# New_Gyro_4_0.net
KiCad netlist of a schematic drawn in Altium Designer
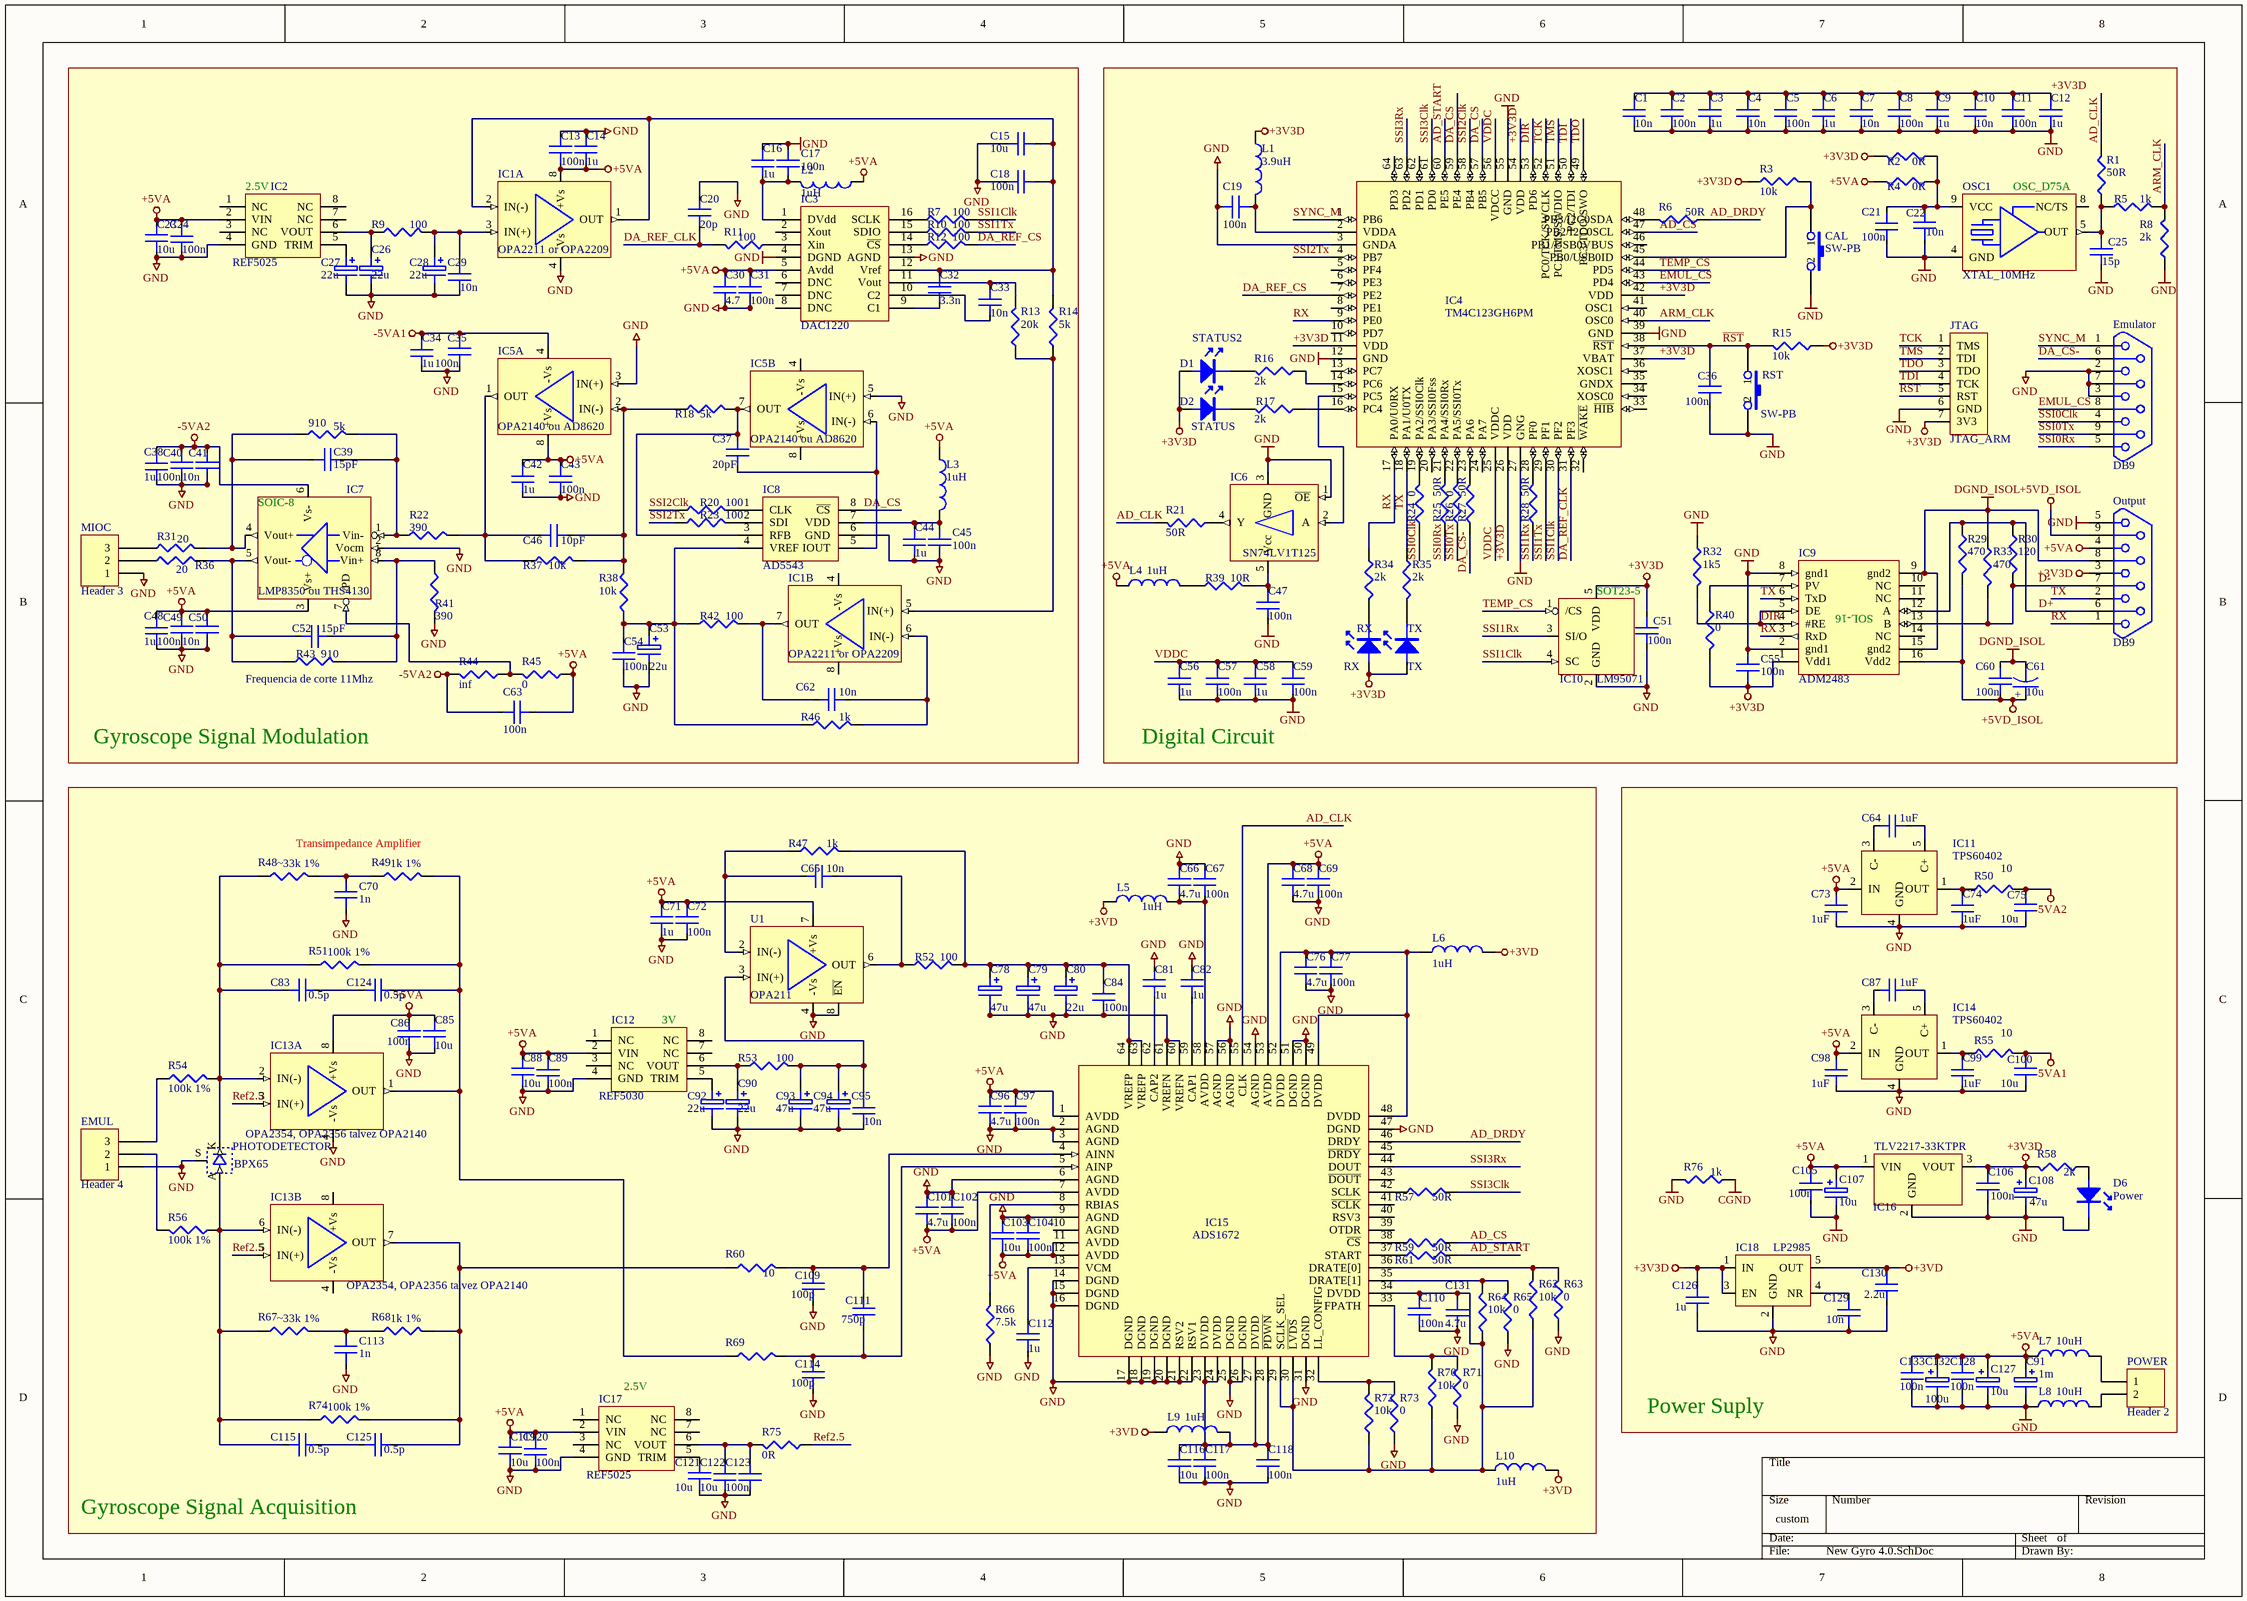
[diagram p0: New Gyro 4.0.SchDoc]

(export (version "E")
  (design (tool "Eeschema 10.0.6"))
  (components
    (comp (ref "910")
      (value "5k")
      (footprint "0805")
      (description "Resistor Thick film 1%")
      (libsource (lib "*") (part "R08"))
    )
    (comp (ref "C1")
      (value "10n")
      (footprint "0805-cap")
      (description "Capacitor Thick film")
      (libsource (lib "*") (part "CAP"))
    )
    (comp (ref "C2")
      (value "100n")
      (footprint "0805-cap")
      (description "Capacitor Thick film")
      (libsource (lib "*") (part "CAP"))
    )
    (comp (ref "C3")
      (value "1u")
      (footprint "0805-cap")
      (description "Capacitor Thick film")
      (libsource (lib "*") (part "CAP"))
    )
    (comp (ref "C4")
      (value "10n")
      (footprint "0805-cap")
      (description "Capacitor Thick film")
      (libsource (lib "*") (part "CAP"))
    )
    (comp (ref "C5")
      (value "100n")
      (footprint "0805-cap")
      (description "Capacitor Thick film")
      (libsource (lib "*") (part "CAP"))
    )
    (comp (ref "C6")
      (value "1u")
      (footprint "0805-cap")
      (description "Capacitor Thick film")
      (libsource (lib "*") (part "CAP"))
    )
    (comp (ref "C7")
      (value "10n")
      (footprint "0805-cap")
      (description "Capacitor Thick film")
      (libsource (lib "*") (part "CAP"))
    )
    (comp (ref "C8")
      (value "100n")
      (footprint "0805-cap")
      (description "Capacitor Thick film")
      (libsource (lib "*") (part "CAP"))
    )
    (comp (ref "C9")
      (value "1u")
      (footprint "0805-cap")
      (description "Capacitor Thick film")
      (libsource (lib "*") (part "CAP"))
    )
    (comp (ref "C10")
      (value "10n")
      (footprint "0805-cap")
      (description "Capacitor Thick film")
      (libsource (lib "*") (part "CAP"))
    )
    (comp (ref "C11")
      (value "100n")
      (footprint "0805-cap")
      (description "Capacitor Thick film")
      (libsource (lib "*") (part "CAP"))
    )
    (comp (ref "C12")
      (value "1u")
      (footprint "0805-cap")
      (description "Capacitor Thick film")
      (libsource (lib "*") (part "CAP"))
    )
    (comp (ref "C13")
      (value "100n")
      (footprint "0805-cap")
      (description "Capacitor Thick film")
      (libsource (lib "*") (part "CAP"))
    )
    (comp (ref "C14")
      (value "1u")
      (footprint "0805-cap")
      (description "Capacitor Thick film")
      (libsource (lib "*") (part "CAP"))
    )
    (comp (ref "C15")
      (value "10u")
      (footprint "0805-cap")
      (description "Capacitor Thick film")
      (libsource (lib "*") (part "CAP"))
    )
    (comp (ref "C16")
      (value "1u")
      (footprint "0805-cap")
      (description "Capacitor Thick film")
      (libsource (lib "*") (part "CAP"))
    )
    (comp (ref "C17")
      (value "100n")
      (footprint "0805-cap")
      (description "Capacitor Thick film")
      (libsource (lib "*") (part "CAP"))
    )
    (comp (ref "C18")
      (value "100n")
      (footprint "0805-cap")
      (description "Capacitor Thick film")
      (libsource (lib "*") (part "CAP"))
    )
    (comp (ref "C19")
      (value "100n")
      (footprint "0805-cap")
      (description "Capacitor Thick film")
      (libsource (lib "*") (part "CAP"))
    )
    (comp (ref "C20")
      (value "20p")
      (footprint "0805-cap")
      (description "Capacitor Thick film")
      (libsource (lib "*") (part "CAP"))
    )
    (comp (ref "C21")
      (value "100n")
      (footprint "0805-cap")
      (description "Capacitor Thick film")
      (libsource (lib "*") (part "CAP"))
    )
    (comp (ref "C22")
      (value "10n")
      (footprint "0805-cap")
      (description "Capacitor Thick film")
      (libsource (lib "*") (part "CAP"))
    )
    (comp (ref "C23")
      (value "10u")
      (footprint "0805-cap")
      (description "Capacitor Thick film")
      (libsource (lib "*") (part "CAP"))
    )
    (comp (ref "C24")
      (value "100n")
      (footprint "0805-cap")
      (description "Capacitor Thick film")
      (libsource (lib "*") (part "CAP"))
    )
    (comp (ref "C25")
      (value "15p")
      (footprint "0805-cap")
      (description "Capacitor Thick film")
      (libsource (lib "*") (part "CAP"))
    )
    (comp (ref "C26")
      (value "22u")
      (footprint "0805-cap")
      (description "Capacitor Tântalo SMD")
      (libsource (lib "*") (part "CAPT"))
    )
    (comp (ref "C27")
      (value "22u")
      (footprint "0805-cap")
      (description "Capacitor Tântalo SMD")
      (libsource (lib "*") (part "CAPT"))
    )
    (comp (ref "C28")
      (value "22u")
      (footprint "0805-cap")
      (description "Capacitor Tântalo SMD")
      (libsource (lib "*") (part "CAPT"))
    )
    (comp (ref "C29")
      (value "10n")
      (footprint "0805-cap")
      (description "Capacitor Thick film")
      (libsource (lib "*") (part "CAP"))
    )
    (comp (ref "C30")
      (value "4.7")
      (footprint "0805-cap")
      (description "Capacitor Thick film")
      (libsource (lib "*") (part "CAP"))
    )
    (comp (ref "C31")
      (value "100n")
      (footprint "0805-cap")
      (description "Capacitor Thick film")
      (libsource (lib "*") (part "CAP"))
    )
    (comp (ref "C32")
      (value "3.3n")
      (footprint "0805-cap")
      (description "Capacitor Thick film")
      (libsource (lib "*") (part "CAP"))
    )
    (comp (ref "C33")
      (value "10n")
      (footprint "0805-cap")
      (description "Capacitor Thick film")
      (libsource (lib "*") (part "CAP"))
    )
    (comp (ref "C34")
      (value "1u")
      (footprint "0805-cap")
      (description "Capacitor Thick film")
      (libsource (lib "*") (part "CAP"))
    )
    (comp (ref "C35")
      (value "100n")
      (footprint "0805-cap")
      (description "Capacitor Thick film")
      (libsource (lib "*") (part "CAP"))
    )
    (comp (ref "C36")
      (value "100n")
      (footprint "0805-cap")
      (description "Capacitor Thick film")
      (libsource (lib "*") (part "CAP"))
    )
    (comp (ref "C37")
      (value "20pF")
      (footprint "0805-cap")
      (description "Capacitor Thick film")
      (libsource (lib "*") (part "CAP"))
    )
    (comp (ref "C38")
      (value "1u")
      (footprint "0805-cap")
      (description "Capacitor Thick film")
      (libsource (lib "*") (part "CAP"))
    )
    (comp (ref "C39")
      (value "15pF")
      (footprint "0805-cap")
      (description "Capacitor Thick film")
      (libsource (lib "*") (part "CAP"))
    )
    (comp (ref "C40")
      (value "100n")
      (footprint "0805-cap")
      (description "Capacitor Thick film")
      (libsource (lib "*") (part "CAP"))
    )
    (comp (ref "C41")
      (value "10n")
      (footprint "0805-cap")
      (description "Capacitor Thick film")
      (libsource (lib "*") (part "CAP"))
    )
    (comp (ref "C42")
      (value "1u")
      (footprint "0805-cap")
      (description "Capacitor Thick film")
      (libsource (lib "*") (part "CAP"))
    )
    (comp (ref "C43")
      (value "100n")
      (footprint "0805-cap")
      (description "Capacitor Thick film")
      (libsource (lib "*") (part "CAP"))
    )
    (comp (ref "C44")
      (value "1u")
      (footprint "0805-cap")
      (description "Capacitor Thick film")
      (libsource (lib "*") (part "CAP"))
    )
    (comp (ref "C45")
      (value "100n")
      (footprint "0805-cap")
      (description "Capacitor Thick film")
      (libsource (lib "*") (part "CAP"))
    )
    (comp (ref "C46")
      (value "10pF")
      (footprint "0805-cap")
      (description "Capacitor Thick film")
      (libsource (lib "*") (part "CAP"))
    )
    (comp (ref "C47")
      (value "100n")
      (footprint "0805-cap")
      (description "Capacitor Thick film")
      (libsource (lib "*") (part "CAP"))
    )
    (comp (ref "C48")
      (value "1u")
      (footprint "0805-cap")
      (description "Capacitor Thick film")
      (libsource (lib "*") (part "CAP"))
    )
    (comp (ref "C49")
      (value "100n")
      (footprint "0805-cap")
      (description "Capacitor Thick film")
      (libsource (lib "*") (part "CAP"))
    )
    (comp (ref "C50")
      (value "10n")
      (footprint "0805-cap")
      (description "Capacitor Thick film")
      (libsource (lib "*") (part "CAP"))
    )
    (comp (ref "C51")
      (value "100n")
      (footprint "0805-cap")
      (description "Capacitor Thick film")
      (libsource (lib "*") (part "CAP"))
    )
    (comp (ref "C52")
      (value "15pF")
      (footprint "0805-cap")
      (description "Capacitor Thick film")
      (libsource (lib "*") (part "CAP"))
    )
    (comp (ref "C53")
      (value "22u")
      (footprint "0805-cap")
      (description "Capacitor Tântalo SMD")
      (libsource (lib "*") (part "CAPT"))
    )
    (comp (ref "C54")
      (value "100n")
      (footprint "0805-cap")
      (description "Capacitor Thick film")
      (libsource (lib "*") (part "CAP"))
    )
    (comp (ref "C55")
      (value "100n")
      (footprint "0805-cap")
      (description "Capacitor Thick film")
      (libsource (lib "*") (part "CAP"))
    )
    (comp (ref "C56")
      (value "1u")
      (footprint "0805-cap")
      (description "Capacitor Thick film")
      (libsource (lib "*") (part "CAP"))
    )
    (comp (ref "C57")
      (value "100n")
      (footprint "0805-cap")
      (description "Capacitor Thick film")
      (libsource (lib "*") (part "CAP"))
    )
    (comp (ref "C58")
      (value "1u")
      (footprint "0805-cap")
      (description "Capacitor Thick film")
      (libsource (lib "*") (part "CAP"))
    )
    (comp (ref "C59")
      (value "100n")
      (footprint "0805-cap")
      (description "Capacitor Thick film")
      (libsource (lib "*") (part "CAP"))
    )
    (comp (ref "C60")
      (value "100n")
      (footprint "0805-cap")
      (description "Capacitor Thick film")
      (libsource (lib "*") (part "CAP"))
    )
    (comp (ref "C61")
      (value "10u")
      (footprint "0805-cap")
      (description "Capacitor Tântalo")
      (libsource (lib "*") (part "CAPACITOR POL"))
    )
    (comp (ref "C62")
      (value "10n")
      (footprint "0805-cap")
      (description "Capacitor Thick film")
      (libsource (lib "*") (part "CAP"))
    )
    (comp (ref "C63")
      (value "100n")
      (footprint "0805-cap")
      (description "Capacitor Thick film")
      (libsource (lib "*") (part "CAP"))
    )
    (comp (ref "C64")
      (value "1uF")
      (footprint "0805-cap")
      (description "Capacitor Thick film")
      (libsource (lib "*") (part "CAP"))
    )
    (comp (ref "C65")
      (value "10n")
      (footprint "0805-cap")
      (description "Capacitor Thick film")
      (libsource (lib "*") (part "CAP"))
    )
    (comp (ref "C66")
      (value "4.7u")
      (footprint "0805-cap")
      (description "Capacitor Thick film")
      (libsource (lib "*") (part "CAP"))
    )
    (comp (ref "C67")
      (value "100n")
      (footprint "0805-cap")
      (description "Capacitor Thick film")
      (libsource (lib "*") (part "CAP"))
    )
    (comp (ref "C68")
      (value "4.7u")
      (footprint "0805-cap")
      (description "Capacitor Thick film")
      (libsource (lib "*") (part "CAP"))
    )
    (comp (ref "C69")
      (value "100n")
      (footprint "0805-cap")
      (description "Capacitor Thick film")
      (libsource (lib "*") (part "CAP"))
    )
    (comp (ref "C70")
      (value "1n")
      (footprint "0805-cap")
      (description "Capacitor Thick film")
      (libsource (lib "*") (part "CAP"))
    )
    (comp (ref "C71")
      (value "1u")
      (footprint "0805-cap")
      (description "Capacitor Thick film")
      (libsource (lib "*") (part "CAP"))
    )
    (comp (ref "C72")
      (value "100n")
      (footprint "0805-cap")
      (description "Capacitor Thick film")
      (libsource (lib "*") (part "CAP"))
    )
    (comp (ref "C73")
      (value "1uF")
      (footprint "0805-cap")
      (description "Capacitor Thick film")
      (libsource (lib "*") (part "CAP"))
    )
    (comp (ref "C74")
      (value "1uF")
      (footprint "0805-cap")
      (description "Capacitor Thick film")
      (libsource (lib "*") (part "CAP"))
    )
    (comp (ref "C75")
      (value "10u")
      (footprint "0805-cap")
      (description "Capacitor Thick film")
      (libsource (lib "*") (part "CAP"))
    )
    (comp (ref "C76")
      (value "4.7u")
      (footprint "0805-cap")
      (description "Capacitor Thick film")
      (libsource (lib "*") (part "CAP"))
    )
    (comp (ref "C77")
      (value "100n")
      (footprint "0805-cap")
      (description "Capacitor Thick film")
      (libsource (lib "*") (part "CAP"))
    )
    (comp (ref "C78")
      (value "47u")
      (footprint "0805-cap")
      (description "Capacitor Tântalo SMD")
      (libsource (lib "*") (part "CAPT"))
    )
    (comp (ref "C79")
      (value "47u")
      (footprint "0805-cap")
      (description "Capacitor Tântalo SMD")
      (libsource (lib "*") (part "CAPT"))
    )
    (comp (ref "C80")
      (value "22u")
      (footprint "0805-cap")
      (description "Capacitor Tântalo SMD")
      (libsource (lib "*") (part "CAPT"))
    )
    (comp (ref "C81")
      (value "1u")
      (footprint "0805-cap")
      (description "Capacitor Thick film")
      (libsource (lib "*") (part "CAP"))
    )
    (comp (ref "C82")
      (value "1u")
      (footprint "0805-cap")
      (description "Capacitor Thick film")
      (libsource (lib "*") (part "CAP"))
    )
    (comp (ref "C83")
      (value "0.5p")
      (footprint "0805-cap")
      (description "Capacitor Thick film")
      (libsource (lib "*") (part "CAP"))
    )
    (comp (ref "C84")
      (value "100n")
      (footprint "0805-cap")
      (description "Capacitor Thick film")
      (libsource (lib "*") (part "CAP"))
    )
    (comp (ref "C85")
      (value "10u")
      (footprint "0805-cap")
      (description "Capacitor Thick film")
      (libsource (lib "*") (part "CAP"))
    )
    (comp (ref "C86")
      (value "100n")
      (footprint "0805-cap")
      (description "Capacitor Thick film")
      (libsource (lib "*") (part "CAP"))
    )
    (comp (ref "C87")
      (value "1uF")
      (footprint "0805-cap")
      (description "Capacitor Thick film")
      (libsource (lib "*") (part "CAP"))
    )
    (comp (ref "C88")
      (value "10u")
      (footprint "0805-cap")
      (description "Capacitor Thick film")
      (libsource (lib "*") (part "CAP"))
    )
    (comp (ref "C89")
      (value "100n")
      (footprint "0805-cap")
      (description "Capacitor Thick film")
      (libsource (lib "*") (part "CAP"))
    )
    (comp (ref "C90")
      (value "22u")
      (footprint "0805-cap")
      (description "Capacitor Tântalo SMD")
      (libsource (lib "*") (part "CAPT"))
    )
    (comp (ref "C91")
      (value "1m")
      (footprint "CAP 1000u - duplicate")
      (description "Capacitor Tântalo SMD")
      (libsource (lib "*") (part "CAPT"))
    )
    (comp (ref "C92")
      (value "22u")
      (footprint "0805-cap")
      (description "Capacitor Tântalo SMD")
      (libsource (lib "*") (part "CAPT"))
    )
    (comp (ref "C93")
      (value "47u")
      (footprint "0805-cap")
      (description "Capacitor Tântalo SMD")
      (libsource (lib "*") (part "CAPT"))
    )
    (comp (ref "C94")
      (value "47u")
      (footprint "0805-cap")
      (description "Capacitor Tântalo SMD")
      (libsource (lib "*") (part "CAPT"))
    )
    (comp (ref "C95")
      (value "10n")
      (footprint "0805-cap")
      (description "Capacitor Thick film")
      (libsource (lib "*") (part "CAP"))
    )
    (comp (ref "C96")
      (value "4.7u")
      (footprint "0805-cap")
      (description "Capacitor Thick film")
      (libsource (lib "*") (part "CAP"))
    )
    (comp (ref "C97")
      (value "100n")
      (footprint "0805-cap")
      (description "Capacitor Thick film")
      (libsource (lib "*") (part "CAP"))
    )
    (comp (ref "C98")
      (value "1uF")
      (footprint "0805-cap")
      (description "Capacitor Thick film")
      (libsource (lib "*") (part "CAP"))
    )
    (comp (ref "C99")
      (value "1uF")
      (footprint "0805-cap")
      (description "Capacitor Thick film")
      (libsource (lib "*") (part "CAP"))
    )
    (comp (ref "C100")
      (value "10u")
      (footprint "0805-cap")
      (description "Capacitor Thick film")
      (libsource (lib "*") (part "CAP"))
    )
    (comp (ref "C101")
      (value "4.7u")
      (footprint "0805-cap")
      (description "Capacitor Thick film")
      (libsource (lib "*") (part "CAP"))
    )
    (comp (ref "C102")
      (value "100n")
      (footprint "0805-cap")
      (description "Capacitor Thick film")
      (libsource (lib "*") (part "CAP"))
    )
    (comp (ref "C103")
      (value "10u")
      (footprint "0805-cap")
      (description "Capacitor Thick film")
      (libsource (lib "*") (part "CAP"))
    )
    (comp (ref "C104")
      (value "100n")
      (footprint "0805-cap")
      (description "Capacitor Thick film")
      (libsource (lib "*") (part "CAP"))
    )
    (comp (ref "C105")
      (value "100n")
      (footprint "0805-cap")
      (description "Capacitor Thick film")
      (libsource (lib "*") (part "CAP"))
    )
    (comp (ref "C106")
      (value "100n")
      (footprint "0805-cap")
      (description "Capacitor Thick film")
      (libsource (lib "*") (part "CAP"))
    )
    (comp (ref "C107")
      (value "10u")
      (footprint "0805-cap")
      (description "Capacitor Tântalo SMD")
      (libsource (lib "*") (part "CAPT"))
    )
    (comp (ref "C108")
      (value "47u")
      (footprint "0805-cap")
      (description "Capacitor Tântalo SMD")
      (libsource (lib "*") (part "CAPT"))
    )
    (comp (ref "C109")
      (value "100p")
      (footprint "0805-cap")
      (description "Capacitor Thick film")
      (libsource (lib "*") (part "CAP"))
    )
    (comp (ref "C110")
      (value "100n")
      (footprint "0805-cap")
      (description "Capacitor Thick film")
      (libsource (lib "*") (part "CAP"))
    )
    (comp (ref "C111")
      (value "750p")
      (footprint "0805-cap")
      (description "Capacitor Thick film")
      (libsource (lib "*") (part "CAP"))
    )
    (comp (ref "C112")
      (value "1u")
      (footprint "0805-cap")
      (description "Capacitor Thick film")
      (libsource (lib "*") (part "CAP"))
    )
    (comp (ref "C113")
      (value "1n")
      (footprint "0805-cap")
      (description "Capacitor Thick film")
      (libsource (lib "*") (part "CAP"))
    )
    (comp (ref "C114")
      (value "100p")
      (footprint "0805-cap")
      (description "Capacitor Thick film")
      (libsource (lib "*") (part "CAP"))
    )
    (comp (ref "C115")
      (value "0.5p")
      (footprint "0805-cap")
      (description "Capacitor Thick film")
      (libsource (lib "*") (part "CAP"))
    )
    (comp (ref "C116")
      (value "10u")
      (footprint "0805-cap")
      (description "Capacitor Thick film")
      (libsource (lib "*") (part "CAP"))
    )
    (comp (ref "C117")
      (value "100n")
      (footprint "0805-cap")
      (description "Capacitor Thick film")
      (libsource (lib "*") (part "CAP"))
    )
    (comp (ref "C118")
      (value "100n")
      (footprint "0805-cap")
      (description "Capacitor Thick film")
      (libsource (lib "*") (part "CAP"))
    )
    (comp (ref "C119")
      (value "10u")
      (footprint "0805-cap")
      (description "Capacitor Thick film")
      (libsource (lib "*") (part "CAP"))
    )
    (comp (ref "C120")
      (value "100n")
      (footprint "0805-cap")
      (description "Capacitor Thick film")
      (libsource (lib "*") (part "CAP"))
    )
    (comp (ref "C121")
      (value "10u")
      (footprint "0805-cap")
      (description "Capacitor Thick film")
      (libsource (lib "*") (part "CAP"))
    )
    (comp (ref "C122")
      (value "10u")
      (footprint "0805-cap")
      (description "Capacitor Thick film")
      (libsource (lib "*") (part "CAP"))
    )
    (comp (ref "C123")
      (value "100n")
      (footprint "0805-cap")
      (description "Capacitor Thick film")
      (libsource (lib "*") (part "CAP"))
    )
    (comp (ref "C124")
      (value "0.5p")
      (footprint "0805-cap")
      (description "Capacitor Thick film")
      (libsource (lib "*") (part "CAP"))
    )
    (comp (ref "C125")
      (value "0.5p")
      (footprint "0805-cap")
      (description "Capacitor Thick film")
      (libsource (lib "*") (part "CAP"))
    )
    (comp (ref "C126")
      (value "1u")
      (footprint "0805-cap")
      (description "Capacitor Thick film")
      (libsource (lib "*") (part "CAP"))
    )
    (comp (ref "C127")
      (value "10u")
      (footprint "0805-cap")
      (description "Capacitor Tântalo SMD")
      (libsource (lib "*") (part "CAPT"))
    )
    (comp (ref "C128")
      (value "100n")
      (footprint "0805-cap")
      (description "Capacitor Thick film")
      (libsource (lib "*") (part "CAP"))
    )
    (comp (ref "C129")
      (value "10n")
      (footprint "0805-cap")
      (description "Capacitor Thick film")
      (libsource (lib "*") (part "CAP"))
    )
    (comp (ref "C130")
      (value "2.2u")
      (footprint "0805-cap")
      (description "Capacitor Thick film")
      (libsource (lib "*") (part "CAP"))
    )
    (comp (ref "C131")
      (value "4.7u")
      (footprint "0805-cap")
      (description "Capacitor Thick film")
      (libsource (lib "*") (part "CAP"))
    )
    (comp (ref "C132")
      (value "100u")
      (footprint "1206_Capacitor")
      (description "Capacitor Tântalo SMD")
      (libsource (lib "*") (part "CAPT"))
    )
    (comp (ref "C133")
      (value "100n")
      (footprint "0805-cap")
      (description "Capacitor Thick film")
      (libsource (lib "*") (part "CAP"))
    )
    (comp (ref "CAL") (value "SW-PB") (footprint "SW SMD") (libsource (lib "Gyro") (part "SW")))
    (comp (ref "D1")
      (value "STATUS2")
      (footprint "LED")
      (description "SMD LED 0805 package")
      (libsource (lib "*") (part "LED_CV"))
    )
    (comp (ref "D2")
      (value "STATUS")
      (footprint "LED")
      (description "SMD LED 0805 package")
      (libsource (lib "*") (part "LED_CV"))
    )
    (comp (ref "D6")
      (value "Power")
      (footprint "LED")
      (description "SMD LED 0805 package")
      (libsource (lib "*") (part "LED_CV"))
    )
    (comp (ref "EMUL")
      (value "Header 4")
      (footprint "HDR1X3")
      (description "Header, 3-Pin")
      (fields (field (name "PUBLISHER") "Altium Limited"))
      (libsource (lib "Miscellaneous Connectors") (part "Header 3"))
    )
    (comp (ref "Emulator") (value "DB9") (footprint "DB9FLW") (libsource (lib "*") (part "DB9")))
    (comp (ref "IC1")
      (value "OPA2211 or OPA2209")
      (footprint "MSOP8")
      (libsource (lib "") (part "AMPOPDUAL_1"))
    )
    (comp (ref "IC2") (value "REF5025") (footprint "MSOP8") (libsource (lib "Gyro") (part "ADR440AMZ")))
    (comp (ref "IC3") (value "DAC1220") (footprint "DBQ 16 TI") (libsource (lib "Gyro") (part "DAC1220")))
    (comp (ref "IC4")
      (value "TM4C123GH6PM")
      (footprint "PQFP64")
      (description "ARM M4F Texas")
      (libsource (lib "Gyro") (part "TM4C123GH6PM"))
    )
    (comp (ref "IC5")
      (value "OPA2140 ou AD8620")
      (footprint "MSOP8")
      (libsource (lib "Gyro") (part "AMPOPDUAL"))
    )
    (comp (ref "IC6")
      (value "SN74LV1T125")
      (footprint "SOT-23-5")
      (description "Single Power Supply Single Buffer Gate with 3-State Output CMOS Logic  Level Shifter")
      (libsource (lib "Gyro") (part "SN74LV1T125"))
    )
    (comp (ref "IC7")
      (value "LMP8350 ou THS4130")
      (footprint "SO-8")
      (description "WIDEBAND, LOW-DISTORTION, FULLY DIFFERENTIAL AMPLIFIER")
      (libsource (lib "*") (part "THS4505"))
    )
    (comp (ref "IC8")
      (value "AD5543")
      (footprint "MSOP8")
      (description "16 Bit SPI DAC")
      (libsource (lib "Gyro") (part "AD5543"))
    )
    (comp (ref "IC9") (value "ADM2483") (footprint "SOL-16") (libsource (lib "*") (part "ADM2483")))
    (comp (ref "IC10") (value "LM95071") (footprint "SOT-23") (libsource (lib "*") (part "LM95071")))
    (comp (ref "IC11")
      (value "TPS60402")
      (footprint "PlacaGiro_atualizada:SOT-23-5")
      (description "Charge Pump Inverter")
      (libsource (lib "Gyro") (part "TPS60401"))
    )
    (comp (ref "IC12") (value "REF5030") (footprint "MSOP8") (libsource (lib "Gyro") (part "ADR440AMZ")))
    (comp (ref "IC13")
      (value "OPA2354, OPA2356 talvez OPA2140")
      (footprint "MSOP8")
      (libsource (lib "") (part "AMPOPDUAL_1"))
    )
    (comp (ref "IC14")
      (value "TPS60402")
      (footprint "PlacaGiro_atualizada:SOT-23-5")
      (description "Charge Pump Inverter")
      (libsource (lib "Gyro") (part "TPS60401"))
    )
    (comp (ref "IC15")
      (value "ADS1672")
      (footprint "TM4C123GH6PM_PQFP64")
      (description "625kSPS, 24-Bit Analog-to-Digital Converter")
      (libsource (lib "Gyro") (part "ADS1672"))
    )
    (comp (ref "IC16")
      (value "TLV2217-33KTPR")
      (footprint "KTP")
      (libsource (lib "*") (part "LM78L05AC/TO3_0"))
    )
    (comp (ref "IC17") (value "REF5025") (footprint "MSOP8") (libsource (lib "Gyro") (part "ADR440AMZ")))
    (comp (ref "IC18")
      (value "LP2985")
      (footprint "PlacaGiro_atualizada:SOT-23-5")
      (libsource (lib "Gyro") (part "LP2985"))
    )
    (comp (ref "JTAG") (value "JTAG_ARM") (footprint "HDR1X7") (libsource (lib "Gyro") (part "JTAG_ARM")))
    (comp (ref "L1") (value "3.9uH") (footprint "0805") (libsource (lib "*") (part "L")))
    (comp (ref "L2") (value "1uH") (footprint "0805") (libsource (lib "*") (part "L")))
    (comp (ref "L3") (value "1uH") (footprint "0805") (libsource (lib "*") (part "L")))
    (comp (ref "L4") (value "1uH") (footprint "0805") (libsource (lib "*") (part "L")))
    (comp (ref "L5") (value "1uH") (footprint "0805") (libsource (lib "*") (part "L")))
    (comp (ref "L6") (value "1uH") (footprint "0805") (libsource (lib "*") (part "L")))
    (comp (ref "L7") (value "10uH") (footprint "SPD62") (libsource (lib "*") (part "L")))
    (comp (ref "L8") (value "10uH") (footprint "SPD62") (libsource (lib "*") (part "L")))
    (comp (ref "L9") (value "1uH") (footprint "0805") (libsource (lib "*") (part "L")))
    (comp (ref "L10") (value "1uH") (footprint "0805") (libsource (lib "*") (part "L")))
    (comp (ref "MIOC")
      (value "Header 3")
      (footprint "HDR1X3")
      (description "Header, 3-Pin")
      (fields (field (name "PUBLISHER") "Altium Limited"))
      (libsource (lib "Miscellaneous Connectors") (part "Header 3"))
    )
    (comp (ref "OSC1")
      (value "XTAL_10MHz")
      (footprint "OSC_D75A_")
      (libsource (lib "Gyro") (part "XTAL_D75A"))
    )
    (comp (ref "Output") (value "DB9") (footprint "DB9FLW") (libsource (lib "") (part "DB9_1")))
    (comp (ref "PHOTODETECTOR") (value "BPX65") (footprint "otico") (libsource (lib "*") (part "BYW29-150")))
    (comp (ref "POWER")
      (value "Header 2")
      (footprint "HDR1X2")
      (description "Header, 2-Pin")
      (fields (field (name "PUBLISHER") "Altium Limited"))
      (libsource (lib "Miscellaneous Connectors") (part "Header 2"))
    )
    (comp (ref "R1")
      (value "50R")
      (footprint "0805")
      (description "Resistor")
      (libsource (lib "*") (part "RES"))
    )
    (comp (ref "R2")
      (value "0R")
      (footprint "0805")
      (description "Resistor Thick film 5%")
      (libsource (lib "*") (part "R06"))
    )
    (comp (ref "R3")
      (value "10k")
      (footprint "0805")
      (description "Resistor Thick film 5%")
      (libsource (lib "*") (part "R06"))
    )
    (comp (ref "R4")
      (value "0R")
      (footprint "0805")
      (description "Resistor Thick film 5%")
      (libsource (lib "*") (part "R06"))
    )
    (comp (ref "R5")
      (value "1k")
      (footprint "0805")
      (description "Resistor")
      (libsource (lib "*") (part "RES"))
    )
    (comp (ref "R6")
      (value "50R")
      (footprint "0805")
      (description "Resistor Thick film 1%")
      (libsource (lib "*") (part "R08"))
    )
    (comp (ref "R7")
      (value "100")
      (footprint "0805")
      (description "Resistor Thick film 1%")
      (libsource (lib "*") (part "R08"))
    )
    (comp (ref "R8")
      (value "2k")
      (footprint "0805")
      (description "Resistor")
      (libsource (lib "*") (part "RES"))
    )
    (comp (ref "R9")
      (value "100")
      (footprint "0805")
      (description "Resistor Thick film 1%")
      (libsource (lib "*") (part "R08"))
    )
    (comp (ref "R10")
      (value "100")
      (footprint "0805")
      (description "Resistor Thick film 1%")
      (libsource (lib "*") (part "R08"))
    )
    (comp (ref "R11")
      (value "100")
      (footprint "0805")
      (description "Resistor Thick film 1%")
      (libsource (lib "*") (part "R08"))
    )
    (comp (ref "R12")
      (value "100")
      (footprint "0805")
      (description "Resistor Thick film 1%")
      (libsource (lib "*") (part "R08"))
    )
    (comp (ref "R13")
      (value "20k")
      (footprint "0805")
      (description "Resistor Thick film 1%")
      (libsource (lib "*") (part "R08"))
    )
    (comp (ref "R14")
      (value "5k")
      (footprint "0805")
      (description "Resistor Thick film 1%")
      (libsource (lib "*") (part "R08"))
    )
    (comp (ref "R15")
      (value "10k")
      (footprint "0805")
      (description "Resistor Thick film 5%")
      (libsource (lib "*") (part "R06"))
    )
    (comp (ref "R16")
      (value "2k")
      (footprint "0805")
      (description "Resistor Thick film 5%")
      (libsource (lib "*") (part "R06"))
    )
    (comp (ref "R17")
      (value "2k")
      (footprint "0805")
      (description "Resistor Thick film 5%")
      (libsource (lib "*") (part "R06"))
    )
    (comp (ref "R18")
      (value "5k")
      (footprint "0805")
      (description "Resistor Thick film 1%")
      (libsource (lib "*") (part "R08"))
    )
    (comp (ref "R20")
      (value "100")
      (footprint "0805")
      (description "Resistor Thick film 1%")
      (libsource (lib "*") (part "R08"))
    )
    (comp (ref "R21")
      (value "50R")
      (footprint "0805")
      (description "Resistor")
      (libsource (lib "*") (part "RES"))
    )
    (comp (ref "R22")
      (value "390")
      (footprint "0805")
      (description "Resistor Thick film 1%")
      (libsource (lib "*") (part "R08"))
    )
    (comp (ref "R23")
      (value "100")
      (footprint "0805")
      (description "Resistor Thick film 1%")
      (libsource (lib "*") (part "R08"))
    )
    (comp (ref "R24")
      (value "0")
      (footprint "0805")
      (description "Resistor Thick film 1%")
      (libsource (lib "*") (part "R08"))
    )
    (comp (ref "R25")
      (value "50R")
      (footprint "0805")
      (description "Resistor Thick film 1%")
      (libsource (lib "*") (part "R08"))
    )
    (comp (ref "R26")
      (value "0")
      (footprint "0805")
      (description "Resistor Thick film 1%")
      (libsource (lib "*") (part "R08"))
    )
    (comp (ref "R27")
      (value "50R")
      (footprint "0805")
      (description "Resistor Thick film 1%")
      (libsource (lib "*") (part "R08"))
    )
    (comp (ref "R28")
      (value "50R")
      (footprint "0805")
      (description "Resistor Thick film 1%")
      (libsource (lib "*") (part "R08"))
    )
    (comp (ref "R29")
      (value "470")
      (footprint "0805")
      (description "Resistor Thick film 5%")
      (libsource (lib "*") (part "R06"))
    )
    (comp (ref "R30")
      (value "120")
      (footprint "0805")
      (description "Resistor Thick film 5%")
      (libsource (lib "*") (part "R06"))
    )
    (comp (ref "R31")
      (value "20")
      (footprint "0805")
      (description "Resistor Thick film 5%")
      (libsource (lib "*") (part "R06"))
    )
    (comp (ref "R32")
      (value "1k5")
      (footprint "0805")
      (description "Resistor Thick film 1%")
      (libsource (lib "*") (part "R08"))
    )
    (comp (ref "R33")
      (value "470")
      (footprint "0805")
      (description "Resistor Thick film 5%")
      (libsource (lib "*") (part "R06"))
    )
    (comp (ref "R34")
      (value "2k")
      (footprint "0805")
      (description "Resistor Thick film 5%")
      (libsource (lib "*") (part "R06"))
    )
    (comp (ref "R35")
      (value "2k")
      (footprint "0805")
      (description "Resistor Thick film 5%")
      (libsource (lib "*") (part "R06"))
    )
    (comp (ref "R36")
      (value "20")
      (footprint "0805")
      (description "Resistor Thick film 5%")
      (libsource (lib "*") (part "R06"))
    )
    (comp (ref "R37")
      (value "10k")
      (footprint "0805")
      (description "Resistor Thick film 1%")
      (libsource (lib "*") (part "R08"))
    )
    (comp (ref "R38")
      (value "10k")
      (footprint "0805")
      (description "Resistor Thick film 1%")
      (libsource (lib "*") (part "R08"))
    )
    (comp (ref "R39")
      (value "10R")
      (footprint "0805")
      (description "Resistor")
      (libsource (lib "*") (part "RES"))
    )
    (comp (ref "R40")
      (value "0")
      (footprint "0805")
      (description "Resistor Thick film 1%")
      (libsource (lib "*") (part "R08"))
    )
    (comp (ref "R41")
      (value "390")
      (footprint "0805")
      (description "Resistor Thick film 1%")
      (libsource (lib "*") (part "R08"))
    )
    (comp (ref "R42")
      (value "100")
      (footprint "0805")
      (description "Resistor Thick film 1%")
      (libsource (lib "*") (part "R08"))
    )
    (comp (ref "R43")
      (value "910")
      (footprint "0805")
      (description "Resistor Thick film 1%")
      (libsource (lib "*") (part "R08"))
    )
    (comp (ref "R44")
      (value "inf")
      (footprint "0805")
      (description "Resistor Thick film 1%")
      (libsource (lib "*") (part "R08"))
    )
    (comp (ref "R45")
      (value "0")
      (footprint "0805")
      (description "Resistor Thick film 1%")
      (libsource (lib "*") (part "R08"))
    )
    (comp (ref "R46")
      (value "1k")
      (footprint "0805")
      (description "Resistor Thick film 1%")
      (libsource (lib "*") (part "R08"))
    )
    (comp (ref "R47")
      (value "1k")
      (footprint "0805")
      (description "Resistor Thick film 1%")
      (libsource (lib "*") (part "R08"))
    )
    (comp (ref "R48")
      (value "~33k 1%")
      (footprint "0805")
      (description "Resistor Thick film 1%")
      (libsource (lib "*") (part "R08"))
    )
    (comp (ref "R49")
      (value "1k 1%")
      (footprint "0805")
      (description "Resistor Thick film 1%")
      (libsource (lib "*") (part "R08"))
    )
    (comp (ref "R50")
      (value "10")
      (footprint "0805")
      (description "Resistor Thick film 1%")
      (libsource (lib "*") (part "R08"))
    )
    (comp (ref "R51")
      (value "100k 1%")
      (footprint "0805")
      (description "Resistor Thick film 1%")
      (libsource (lib "*") (part "R08"))
    )
    (comp (ref "R52")
      (value "100")
      (footprint "0805")
      (description "Resistor Thick film 1%")
      (libsource (lib "*") (part "R08"))
    )
    (comp (ref "R53")
      (value "100")
      (footprint "0805")
      (description "Resistor Thick film 1%")
      (libsource (lib "*") (part "R08"))
    )
    (comp (ref "R54")
      (value "100k 1%")
      (footprint "0805")
      (description "Resistor Thick film 1%")
      (libsource (lib "*") (part "R08"))
    )
    (comp (ref "R55")
      (value "10")
      (footprint "0805")
      (description "Resistor Thick film 1%")
      (libsource (lib "*") (part "R08"))
    )
    (comp (ref "R56")
      (value "100k 1%")
      (footprint "0805")
      (description "Resistor Thick film 1%")
      (libsource (lib "*") (part "R08"))
    )
    (comp (ref "R57")
      (value "50R")
      (footprint "0805")
      (description "Resistor Thick film 1%")
      (libsource (lib "*") (part "R08"))
    )
    (comp (ref "R58")
      (value "2k")
      (footprint "0805")
      (description "Resistor Thick film 5%")
      (libsource (lib "*") (part "R06"))
    )
    (comp (ref "R59")
      (value "50R")
      (footprint "0805")
      (description "Resistor Thick film 1%")
      (libsource (lib "*") (part "R08"))
    )
    (comp (ref "R60")
      (value "10")
      (footprint "0805")
      (description "Resistor Thick film 1%")
      (libsource (lib "*") (part "R08"))
    )
    (comp (ref "R61")
      (value "50R")
      (footprint "0805")
      (description "Resistor Thick film 1%")
      (libsource (lib "*") (part "R08"))
    )
    (comp (ref "R62")
      (value "10k")
      (footprint "0805")
      (description "Resistor Thick film 1%")
      (libsource (lib "*") (part "R08"))
    )
    (comp (ref "R63")
      (value "0")
      (footprint "0805")
      (description "Resistor Thick film 1%")
      (libsource (lib "*") (part "R08"))
    )
    (comp (ref "R64")
      (value "10k")
      (footprint "0805")
      (description "Resistor Thick film 1%")
      (libsource (lib "*") (part "R08"))
    )
    (comp (ref "R65")
      (value "0")
      (footprint "0805")
      (description "Resistor Thick film 1%")
      (libsource (lib "*") (part "R08"))
    )
    (comp (ref "R66")
      (value "7.5k")
      (footprint "0805")
      (description "Resistor Thick film 1%")
      (libsource (lib "*") (part "R08"))
    )
    (comp (ref "R67")
      (value "~33k 1%")
      (footprint "0805")
      (description "Resistor Thick film 1%")
      (libsource (lib "*") (part "R08"))
    )
    (comp (ref "R68")
      (value "1k 1%")
      (footprint "0805")
      (description "Resistor Thick film 1%")
      (libsource (lib "*") (part "R08"))
    )
    (comp (ref "R69")
      (value "~")
      (footprint "0805")
      (description "Resistor Thick film 1%")
      (libsource (lib "*") (part "R08"))
    )
    (comp (ref "R70")
      (value "10k")
      (footprint "0805")
      (description "Resistor Thick film 1%")
      (libsource (lib "*") (part "R08"))
    )
    (comp (ref "R71")
      (value "0")
      (footprint "0805")
      (description "Resistor Thick film 1%")
      (libsource (lib "*") (part "R08"))
    )
    (comp (ref "R72")
      (value "10k")
      (footprint "0805")
      (description "Resistor Thick film 1%")
      (libsource (lib "*") (part "R08"))
    )
    (comp (ref "R73")
      (value "0")
      (footprint "0805")
      (description "Resistor Thick film 1%")
      (libsource (lib "*") (part "R08"))
    )
    (comp (ref "R74")
      (value "100k 1%")
      (footprint "0805")
      (description "Resistor Thick film 1%")
      (libsource (lib "*") (part "R08"))
    )
    (comp (ref "R75")
      (value "0R")
      (footprint "0805")
      (description "Resistor Thick film 5%")
      (libsource (lib "*") (part "R06"))
    )
    (comp (ref "R76")
      (value "1k")
      (footprint "0805")
      (description "Resistor Thick film 5%")
      (libsource (lib "*") (part "R06"))
    )
    (comp (ref "RST") (value "SW-PB") (footprint "SW SMD") (libsource (lib "Gyro") (part "SW")))
    (comp (ref "RX")
      (value "RX")
      (footprint "LED")
      (description "SMD LED 0805 package")
      (libsource (lib "*") (part "LED_CV"))
    )
    (comp (ref "TX")
      (value "TX")
      (footprint "LED")
      (description "SMD LED 0805 package")
      (libsource (lib "*") (part "LED_CV"))
    )
    (comp (ref "U1") (value "OPA211") (footprint "MSOP8") (libsource (lib "Gyro") (part "OPA211")))
  )
  (nets
    (net (code "1") (name "+3V3D") (class "Default")
      (node (ref "C1") (pin "2") (pinfunction "2_2") (pintype "passive"))
      (node (ref "C10") (pin "2") (pinfunction "2_2") (pintype "passive"))
      (node (ref "C106") (pin "2") (pinfunction "2_2") (pintype "passive"))
      (node (ref "C108") (pin "1") (pinfunction "+_1") (pintype "passive"))
      (node (ref "C11") (pin "2") (pinfunction "2_2") (pintype "passive"))
      (node (ref "C12") (pin "2") (pinfunction "2_2") (pintype "passive"))
      (node (ref "C126") (pin "2") (pinfunction "2_2") (pintype "passive"))
      (node (ref "C2") (pin "2") (pinfunction "2_2") (pintype "passive"))
      (node (ref "C3") (pin "2") (pinfunction "2_2") (pintype "passive"))
      (node (ref "C4") (pin "2") (pinfunction "2_2") (pintype "passive"))
      (node (ref "C5") (pin "2") (pinfunction "2_2") (pintype "passive"))
      (node (ref "C51") (pin "2") (pinfunction "2_2") (pintype "passive"))
      (node (ref "C55") (pin "2") (pinfunction "2_2") (pintype "passive"))
      (node (ref "C6") (pin "2") (pinfunction "2_2") (pintype "passive"))
      (node (ref "C7") (pin "2") (pinfunction "2_2") (pintype "passive"))
      (node (ref "C8") (pin "2") (pinfunction "2_2") (pintype "passive"))
      (node (ref "C9") (pin "2") (pinfunction "2_2") (pintype "passive"))
      (node (ref "D1") (pin "A") (pinfunction "a_A") (pintype "passive"))
      (node (ref "D2") (pin "A") (pinfunction "a_A") (pintype "passive"))
      (node (ref "IC10") (pin "5") (pinfunction "VDD_5") (pintype "power_in"))
      (node (ref "IC16") (pin "3") (pinfunction "VOUT_3") (pintype "power_in"))
      (node (ref "IC18") (pin "1") (pinfunction "IN_1") (pintype "passive"))
      (node (ref "IC18") (pin "3") (pinfunction "EN_3") (pintype "passive"))
      (node (ref "IC4") (pin "11") (pinfunction "VDD_11") (pintype "power_in"))
      (node (ref "IC4") (pin "26") (pinfunction "VDD_26") (pintype "power_in"))
      (node (ref "IC4") (pin "37") (pinfunction "VBAT_37") (pintype "power_in"))
      (node (ref "IC4") (pin "42") (pinfunction "VDD_42") (pintype "power_in"))
      (node (ref "IC4") (pin "54") (pinfunction "VDD_54") (pintype "power_in"))
      (node (ref "IC9") (pin "1") (pinfunction "Vdd1_1") (pintype "power_in"))
      (node (ref "JTAG") (pin "7") (pinfunction "3V3_7") (pintype "passive"))
      (node (ref "L1") (pin "1") (pinfunction "1_1") (pintype "passive"))
      (node (ref "Output") (pin "3") (pinfunction "3_3") (pintype "passive"))
      (node (ref "R15") (pin "1") (pinfunction "1_1") (pintype "passive"))
      (node (ref "R2") (pin "2") (pinfunction "2_2") (pintype "passive"))
      (node (ref "R3") (pin "1") (pinfunction "1_1") (pintype "passive"))
      (node (ref "R40") (pin "2") (pinfunction "2_2") (pintype "passive"))
      (node (ref "R58") (pin "2") (pinfunction "2_2") (pintype "passive"))
      (node (ref "RX") (pin "A") (pinfunction "a_A") (pintype "passive"))
      (node (ref "TX") (pin "A") (pinfunction "a_A") (pintype "passive"))
    )
    (net (code "2") (name "+3VD") (class "Default")
      (node (ref "C130") (pin "2") (pinfunction "2_2") (pintype "passive"))
      (node (ref "IC18") (pin "5") (pinfunction "OUT_5") (pintype "passive"))
      (node (ref "L10") (pin "2") (pinfunction "2_2") (pintype "passive"))
      (node (ref "L5") (pin "1") (pinfunction "1_1") (pintype "passive"))
      (node (ref "L6") (pin "2") (pinfunction "2_2") (pintype "passive"))
      (node (ref "L9") (pin "1") (pinfunction "1_1") (pintype "passive"))
    )
    (net (code "3") (name "+5VA") (class "Default")
      (node (ref "C101") (pin "2") (pinfunction "2_2") (pintype "passive"))
      (node (ref "C102") (pin "2") (pinfunction "2_2") (pintype "passive"))
      (node (ref "C103") (pin "2") (pinfunction "2_2") (pintype "passive"))
      (node (ref "C104") (pin "2") (pinfunction "2_2") (pintype "passive"))
      (node (ref "C105") (pin "2") (pinfunction "2_2") (pintype "passive"))
      (node (ref "C107") (pin "1") (pinfunction "+_1") (pintype "passive"))
      (node (ref "C119") (pin "1") (pinfunction "1_1") (pintype "passive"))
      (node (ref "C120") (pin "2") (pinfunction "2_2") (pintype "passive"))
      (node (ref "C127") (pin "1") (pinfunction "+_1") (pintype "passive"))
      (node (ref "C128") (pin "2") (pinfunction "2_2") (pintype "passive"))
      (node (ref "C13") (pin "2") (pinfunction "2_2") (pintype "passive"))
      (node (ref "C132") (pin "1") (pinfunction "+_1") (pintype "passive"))
      (node (ref "C133") (pin "2") (pinfunction "2_2") (pintype "passive"))
      (node (ref "C14") (pin "2") (pinfunction "2_2") (pintype "passive"))
      (node (ref "C23") (pin "1") (pinfunction "1_1") (pintype "passive"))
      (node (ref "C24") (pin "2") (pinfunction "2_2") (pintype "passive"))
      (node (ref "C30") (pin "2") (pinfunction "2_2") (pintype "passive"))
      (node (ref "C31") (pin "2") (pinfunction "2_2") (pintype "passive"))
      (node (ref "C42") (pin "2") (pinfunction "2_2") (pintype "passive"))
      (node (ref "C43") (pin "2") (pinfunction "2_2") (pintype "passive"))
      (node (ref "C48") (pin "2") (pinfunction "2_2") (pintype "passive"))
      (node (ref "C49") (pin "1") (pinfunction "1_1") (pintype "passive"))
      (node (ref "C50") (pin "1") (pinfunction "1_1") (pintype "passive"))
      (node (ref "C63") (pin "1") (pinfunction "1_1") (pintype "passive"))
      (node (ref "C68") (pin "1") (pinfunction "1_1") (pintype "passive"))
      (node (ref "C69") (pin "1") (pinfunction "1_1") (pintype "passive"))
      (node (ref "C71") (pin "1") (pinfunction "1_1") (pintype "passive"))
      (node (ref "C72") (pin "1") (pinfunction "1_1") (pintype "passive"))
      (node (ref "C73") (pin "2") (pinfunction "2_2") (pintype "passive"))
      (node (ref "C85") (pin "1") (pinfunction "1_1") (pintype "passive"))
      (node (ref "C86") (pin "1") (pinfunction "1_1") (pintype "passive"))
      (node (ref "C88") (pin "1") (pinfunction "1_1") (pintype "passive"))
      (node (ref "C89") (pin "2") (pinfunction "2_2") (pintype "passive"))
      (node (ref "C91") (pin "1") (pinfunction "+_1") (pintype "passive"))
      (node (ref "C96") (pin "1") (pinfunction "1_1") (pintype "passive"))
      (node (ref "C97") (pin "1") (pinfunction "1_1") (pintype "passive"))
      (node (ref "C98") (pin "2") (pinfunction "2_2") (pintype "passive"))
      (node (ref "IC1") (pin "8") (pinfunction "+Vs_8") (pintype "power_in"))
      (node (ref "IC11") (pin "2") (pinfunction "IN_2") (pintype "passive"))
      (node (ref "IC12") (pin "2") (pinfunction "VIN_2") (pintype "passive"))
      (node (ref "IC13") (pin "8") (pinfunction "+Vs_8") (pintype "power_in"))
      (node (ref "IC14") (pin "2") (pinfunction "IN_2") (pintype "passive"))
      (node (ref "IC15") (pin "1") (pinfunction "AVDD_1") (pintype "power_in"))
      (node (ref "IC15") (pin "11") (pinfunction "AVDD_11") (pintype "power_in"))
      (node (ref "IC15") (pin "12") (pinfunction "AVDD_12") (pintype "power_in"))
      (node (ref "IC15") (pin "53") (pinfunction "AVDD_53") (pintype "power_in"))
      (node (ref "IC15") (pin "7") (pinfunction "AVDD_7") (pintype "power_in"))
      (node (ref "IC16") (pin "1") (pinfunction "VIN_1") (pintype "power_in"))
      (node (ref "IC17") (pin "2") (pinfunction "VIN_2") (pintype "passive"))
      (node (ref "IC2") (pin "2") (pinfunction "VIN_2") (pintype "passive"))
      (node (ref "IC3") (pin "5") (pinfunction "Avdd_5") (pintype "power_in"))
      (node (ref "IC5") (pin "8") (pinfunction "+Vs_8") (pintype "power_in"))
      (node (ref "IC7") (pin "3") (pinfunction "Vs+_3") (pintype "power_in"))
      (node (ref "L2") (pin "1") (pinfunction "1_1") (pintype "passive"))
      (node (ref "L3") (pin "1") (pinfunction "1_1") (pintype "passive"))
      (node (ref "L4") (pin "1") (pinfunction "1_1") (pintype "passive"))
      (node (ref "L7") (pin "1") (pinfunction "1_1") (pintype "passive"))
      (node (ref "Output") (pin "4") (pinfunction "4_4") (pintype "passive"))
      (node (ref "R4") (pin "2") (pinfunction "2_2") (pintype "passive"))
      (node (ref "R45") (pin "1") (pinfunction "1_1") (pintype "passive"))
      (node (ref "U1") (pin "7") (pinfunction "+Vs_7") (pintype "power_in"))
    )
    (net (code "4") (name "+5VD_ISOL") (class "Default")
      (node (ref "C60") (pin "1") (pinfunction "1_1") (pintype "passive"))
      (node (ref "C61") (pin "1") (pinfunction "1_1") (pintype "passive"))
      (node (ref "IC9") (pin "16") (pinfunction "Vdd2_16") (pintype "power_in"))
      (node (ref "Output") (pin "9") (pinfunction "9_9") (pintype "passive"))
      (node (ref "R29") (pin "2") (pinfunction "2_2") (pintype "passive"))
    )
    (net (code "5") (name "-5VA1") (class "Default")
      (node (ref "C100") (pin "1") (pinfunction "1_1") (pintype "passive"))
      (node (ref "C34") (pin "2") (pinfunction "2_2") (pintype "passive"))
      (node (ref "C35") (pin "1") (pinfunction "1_1") (pintype "passive"))
      (node (ref "IC5") (pin "4") (pinfunction "-Vs_4") (pintype "power_in"))
      (node (ref "R55") (pin "2") (pinfunction "2_2") (pintype "passive"))
    )
    (net (code "6") (name "-5VA2") (class "Default")
      (node (ref "C38") (pin "2") (pinfunction "2_2") (pintype "passive"))
      (node (ref "C40") (pin "1") (pinfunction "1_1") (pintype "passive"))
      (node (ref "C41") (pin "1") (pinfunction "1_1") (pintype "passive"))
      (node (ref "C63") (pin "2") (pinfunction "2_2") (pintype "passive"))
      (node (ref "C75") (pin "1") (pinfunction "1_1") (pintype "passive"))
      (node (ref "IC7") (pin "6") (pinfunction "Vs-_6") (pintype "power_in"))
      (node (ref "R44") (pin "2") (pinfunction "2_2") (pintype "passive"))
      (node (ref "R50") (pin "2") (pinfunction "2_2") (pintype "passive"))
    )
    (net (code "7") (name "/AD_CLK") (class "Default")
      (node (ref "IC15") (pin "55") (pinfunction "CLK_55") (pintype "power_in"))
      (node (ref "R1") (pin "2") (pinfunction "2_2") (pintype "passive"))
      (node (ref "R21") (pin "2") (pinfunction "2_2") (pintype "passive"))
    )
    (net (code "8") (name "/AD_CS") (class "Default")
      (node (ref "IC4") (pin "47") (pinfunction "PB2/I2C0SCL_47") (pintype "bidirectional"))
      (node (ref "R59") (pin "2") (pinfunction "2_2") (pintype "passive"))
    )
    (net (code "9") (name "/AD_DRDY") (class "Default")
      (node (ref "IC15") (pin "46") (pinfunction "DRDY_46") (pintype "power_in"))
      (node (ref "R6") (pin "1") (pinfunction "1_1") (pintype "passive"))
    )
    (net (code "10") (name "/AD_START") (class "Default")
      (node (ref "IC4") (pin "60") (pinfunction "PE5_60") (pintype "bidirectional"))
      (node (ref "R61") (pin "2") (pinfunction "2_2") (pintype "passive"))
    )
    (net (code "11") (name "/ARM_CLK") (class "Default")
      (node (ref "IC4") (pin "40") (pinfunction "OSC0_40") (pintype "input"))
      (node (ref "R5") (pin "2") (pinfunction "2_2") (pintype "passive"))
      (node (ref "R8") (pin "2") (pinfunction "2_2") (pintype "passive"))
    )
    (net (code "12") (name "/D+") (class "Default")
      (node (ref "IC9") (pin "12") (pinfunction "A_12") (pintype "bidirectional"))
      (node (ref "Output") (pin "6") (pinfunction "6_6") (pintype "passive"))
      (node (ref "R29") (pin "1") (pinfunction "1_1") (pintype "passive"))
      (node (ref "R30") (pin "1") (pinfunction "1_1") (pintype "passive"))
    )
    (net (code "13") (name "/D-") (class "Default")
      (node (ref "IC9") (pin "13") (pinfunction "B_13") (pintype "bidirectional"))
      (node (ref "Output") (pin "7") (pinfunction "7_7") (pintype "passive"))
      (node (ref "R30") (pin "2") (pinfunction "2_2") (pintype "passive"))
      (node (ref "R33") (pin "2") (pinfunction "2_2") (pintype "passive"))
    )
    (net (code "14") (name "/DA_CS") (class "Default")
      (node (ref "IC4") (pin "57") (pinfunction "PB5_57") (pintype "bidirectional"))
      (node (ref "IC4") (pin "59") (pinfunction "PE4_59") (pintype "bidirectional"))
      (node (ref "IC8") (pin "8") (pinfunction "~{CS}_8") (pintype "passive"))
    )
    (net (code "15") (name "/DA_CS-") (class "Default")
      (node (ref "Emulator") (pin "6") (pinfunction "6_6") (pintype "passive"))
      (node (ref "R27") (pin "1") (pinfunction "1_1") (pintype "passive"))
    )
    (net (code "16") (name "/DA_REF_CLK") (class "Default")
      (node (ref "C20") (pin "2") (pinfunction "2_2") (pintype "passive"))
      (node (ref "IC4") (pin "31") (pinfunction "PF3_31") (pintype "bidirectional"))
      (node (ref "R11") (pin "2") (pinfunction "2_2") (pintype "passive"))
    )
    (net (code "17") (name "/DA_REF_CS") (class "Default")
      (node (ref "IC4") (pin "7") (pinfunction "PE2_7") (pintype "bidirectional"))
      (node (ref "R12") (pin "2") (pinfunction "2_2") (pintype "passive"))
    )
    (net (code "18") (name "/DIR") (class "Default")
      (node (ref "IC4") (pin "53") (pinfunction "PD6_53") (pintype "bidirectional"))
      (node (ref "IC9") (pin "4") (pinfunction "#RE_4") (pintype "input"))
      (node (ref "IC9") (pin "5") (pinfunction "DE_5") (pintype "input"))
      (node (ref "R32") (pin "2") (pinfunction "2_2") (pintype "passive"))
    )
    (net (code "19") (name "/EMUL_CS") (class "Default")
      (node (ref "Emulator") (pin "8") (pinfunction "8_8") (pintype "passive"))
      (node (ref "IC4") (pin "43") (pinfunction "PD4_43") (pintype "bidirectional"))
    )
    (net (code "20") (name "/RX") (class "Default")
      (node (ref "IC4") (pin "17") (pinfunction "PA0/U0RX_17") (pintype "bidirectional"))
      (node (ref "IC4") (pin "9") (pinfunction "PE0_9") (pintype "bidirectional"))
      (node (ref "IC9") (pin "3") (pinfunction "RxD_3") (pintype "output"))
      (node (ref "Output") (pin "1") (pinfunction "1_1") (pintype "passive"))
      (node (ref "R34") (pin "1") (pinfunction "1_1") (pintype "passive"))
    )
    (net (code "21") (name "/Ref2.5") (class "Default")
      (node (ref "IC13") (pin "3") (pinfunction "IN(+)_3") (pintype "input"))
      (node (ref "IC13") (pin "5") (pinfunction "IN(+)_5") (pintype "input"))
      (node (ref "R75") (pin "1") (pinfunction "1_1") (pintype "passive"))
    )
    (net (code "22") (name "/SSI0Clk") (class "Default")
      (node (ref "Emulator") (pin "4") (pinfunction "4_4") (pintype "passive"))
      (node (ref "R24") (pin "1") (pinfunction "1_1") (pintype "passive"))
    )
    (net (code "23") (name "/SSI0Rx") (class "Default")
      (node (ref "Emulator") (pin "5") (pinfunction "5_5") (pintype "passive"))
      (node (ref "R25") (pin "1") (pinfunction "1_1") (pintype "passive"))
    )
    (net (code "24") (name "/SSI0Tx") (class "Default")
      (node (ref "Emulator") (pin "9") (pinfunction "9_9") (pintype "passive"))
      (node (ref "R26") (pin "1") (pinfunction "1_1") (pintype "passive"))
    )
    (net (code "25") (name "/SSI1Clk") (class "Default")
      (node (ref "IC10") (pin "4") (pinfunction "SC_4") (pintype "input"))
      (node (ref "IC4") (pin "30") (pinfunction "PF2_30") (pintype "bidirectional"))
      (node (ref "R7") (pin "2") (pinfunction "2_2") (pintype "passive"))
    )
    (net (code "26") (name "/SSI1Rx") (class "Default")
      (node (ref "IC10") (pin "3") (pinfunction "SI/O_3") (pintype "bidirectional"))
      (node (ref "R28") (pin "1") (pinfunction "1_1") (pintype "passive"))
    )
    (net (code "27") (name "/SSI1Tx") (class "Default")
      (node (ref "IC4") (pin "29") (pinfunction "PF1_29") (pintype "bidirectional"))
      (node (ref "R10") (pin "2") (pinfunction "2_2") (pintype "passive"))
    )
    (net (code "28") (name "/SSI2Clk") (class "Default")
      (node (ref "IC4") (pin "58") (pinfunction "PB4_58") (pintype "bidirectional"))
      (node (ref "R20") (pin "1") (pinfunction "1_1") (pintype "passive"))
    )
    (net (code "29") (name "/SSI2Tx") (class "Default")
      (node (ref "IC4") (pin "4") (pinfunction "PB7_4") (pintype "bidirectional"))
      (node (ref "R23") (pin "1") (pinfunction "1_1") (pintype "passive"))
    )
    (net (code "30") (name "/SSI3Clk") (class "Default")
      (node (ref "IC4") (pin "61") (pinfunction "PD0_61") (pintype "bidirectional"))
      (node (ref "R57") (pin "2") (pinfunction "2_2") (pintype "passive"))
    )
    (net (code "31") (name "/SSI3Rx") (class "Default")
      (node (ref "IC15") (pin "44") (pinfunction "DOUT_44") (pintype "power_in"))
      (node (ref "IC4") (pin "63") (pinfunction "PD2_63") (pintype "bidirectional"))
    )
    (net (code "32") (name "/SYNC_M") (class "Default")
      (node (ref "Emulator") (pin "1") (pinfunction "1_1") (pintype "passive"))
      (node (ref "IC4") (pin "1") (pinfunction "PB6_1") (pintype "bidirectional"))
    )
    (net (code "33") (name "/TCK") (class "Default")
      (node (ref "IC4") (pin "52") (pinfunction "PC0/TCK/SWCLK_52") (pintype "bidirectional"))
      (node (ref "JTAG") (pin "1") (pinfunction "TMS_1") (pintype "passive"))
    )
    (net (code "34") (name "/TDI") (class "Default")
      (node (ref "IC4") (pin "50") (pinfunction "PC2/TDI_50") (pintype "bidirectional"))
      (node (ref "JTAG") (pin "4") (pinfunction "TCK_4") (pintype "passive"))
    )
    (net (code "35") (name "/TDO") (class "Default")
      (node (ref "IC4") (pin "49") (pinfunction "PC3/TDO/SWO_49") (pintype "bidirectional"))
      (node (ref "JTAG") (pin "3") (pinfunction "TDO_3") (pintype "passive"))
    )
    (net (code "36") (name "/TEMP_CS") (class "Default")
      (node (ref "IC10") (pin "1") (pinfunction "/CS_1") (pintype "input"))
      (node (ref "IC4") (pin "44") (pinfunction "PD5_44") (pintype "bidirectional"))
    )
    (net (code "37") (name "/TMS") (class "Default")
      (node (ref "IC4") (pin "51") (pinfunction "PC1/TMS/SWDIO_51") (pintype "bidirectional"))
      (node (ref "JTAG") (pin "2") (pinfunction "TDI_2") (pintype "passive"))
    )
    (net (code "38") (name "/TX") (class "Default")
      (node (ref "IC4") (pin "18") (pinfunction "PA1/U0TX_18") (pintype "bidirectional"))
      (node (ref "IC9") (pin "6") (pinfunction "TxD_6") (pintype "input"))
      (node (ref "Output") (pin "2") (pinfunction "2_2") (pintype "passive"))
      (node (ref "R35") (pin "1") (pinfunction "1_1") (pintype "passive"))
    )
    (net (code "39") (name "/VDDC") (class "Default")
      (node (ref "C56") (pin "2") (pinfunction "2_2") (pintype "passive"))
      (node (ref "C57") (pin "2") (pinfunction "2_2") (pintype "passive"))
      (node (ref "C58") (pin "2") (pinfunction "2_2") (pintype "passive"))
      (node (ref "C59") (pin "2") (pinfunction "2_2") (pintype "passive"))
      (node (ref "IC4") (pin "25") (pinfunction "VDDC_25") (pintype "power_in"))
      (node (ref "IC4") (pin "56") (pinfunction "VDCC_56") (pintype "power_in"))
    )
    (net (code "40") (name "/~{RST}") (class "Default")
      (node (ref "C36") (pin "1") (pinfunction "1_1") (pintype "passive"))
      (node (ref "IC4") (pin "38") (pinfunction "~{RST}_38") (pintype "input"))
      (node (ref "JTAG") (pin "5") (pinfunction "RST_5") (pintype "passive"))
      (node (ref "R15") (pin "2") (pinfunction "2_2") (pintype "passive"))
      (node (ref "RST") (pin "1") (pinfunction "1_1") (pintype "passive"))
    )
    (net (code "41") (name "CGND") (class "Default")
      (node (ref "R76") (pin "1") (pinfunction "1_1") (pintype "passive"))
    )
    (net (code "42") (name "DGND_ISOL") (class "Default")
      (node (ref "C60") (pin "2") (pinfunction "2_2") (pintype "passive"))
      (node (ref "C61") (pin "2") (pinfunction "2_2") (pintype "passive"))
      (node (ref "IC9") (pin "15") (pinfunction "gnd2_15") (pintype "power_in"))
      (node (ref "IC9") (pin "9") (pinfunction "gnd2_9") (pintype "power_in"))
      (node (ref "Output") (pin "8") (pinfunction "8_8") (pintype "passive"))
      (node (ref "R33") (pin "1") (pinfunction "1_1") (pintype "passive"))
    )
    (net (code "43") (name "GND") (class "Default")
      (node (ref "C1") (pin "1") (pinfunction "1_1") (pintype "passive"))
      (node (ref "C10") (pin "1") (pinfunction "1_1") (pintype "passive"))
      (node (ref "C100") (pin "2") (pinfunction "2_2") (pintype "passive"))
      (node (ref "C101") (pin "1") (pinfunction "1_1") (pintype "passive"))
      (node (ref "C102") (pin "1") (pinfunction "1_1") (pintype "passive"))
      (node (ref "C103") (pin "1") (pinfunction "1_1") (pintype "passive"))
      (node (ref "C104") (pin "1") (pinfunction "1_1") (pintype "passive"))
      (node (ref "C105") (pin "1") (pinfunction "1_1") (pintype "passive"))
      (node (ref "C106") (pin "1") (pinfunction "1_1") (pintype "passive"))
      (node (ref "C107") (pin "2") (pinfunction "-_2") (pintype "passive"))
      (node (ref "C108") (pin "2") (pinfunction "-_2") (pintype "passive"))
      (node (ref "C109") (pin "2") (pinfunction "2_2") (pintype "passive"))
      (node (ref "C11") (pin "1") (pinfunction "1_1") (pintype "passive"))
      (node (ref "C110") (pin "2") (pinfunction "2_2") (pintype "passive"))
      (node (ref "C112") (pin "2") (pinfunction "2_2") (pintype "passive"))
      (node (ref "C113") (pin "2") (pinfunction "2_2") (pintype "passive"))
      (node (ref "C114") (pin "2") (pinfunction "2_2") (pintype "passive"))
      (node (ref "C116") (pin "2") (pinfunction "2_2") (pintype "passive"))
      (node (ref "C117") (pin "2") (pinfunction "2_2") (pintype "passive"))
      (node (ref "C118") (pin "2") (pinfunction "2_2") (pintype "passive"))
      (node (ref "C119") (pin "2") (pinfunction "2_2") (pintype "passive"))
      (node (ref "C12") (pin "1") (pinfunction "1_1") (pintype "passive"))
      (node (ref "C120") (pin "1") (pinfunction "1_1") (pintype "passive"))
      (node (ref "C121") (pin "2") (pinfunction "2_2") (pintype "passive"))
      (node (ref "C122") (pin "1") (pinfunction "1_1") (pintype "passive"))
      (node (ref "C123") (pin "1") (pinfunction "1_1") (pintype "passive"))
      (node (ref "C126") (pin "1") (pinfunction "1_1") (pintype "passive"))
      (node (ref "C127") (pin "2") (pinfunction "-_2") (pintype "passive"))
      (node (ref "C128") (pin "1") (pinfunction "1_1") (pintype "passive"))
      (node (ref "C129") (pin "1") (pinfunction "1_1") (pintype "passive"))
      (node (ref "C13") (pin "1") (pinfunction "1_1") (pintype "passive"))
      (node (ref "C130") (pin "1") (pinfunction "1_1") (pintype "passive"))
      (node (ref "C131") (pin "1") (pinfunction "1_1") (pintype "passive"))
      (node (ref "C132") (pin "2") (pinfunction "-_2") (pintype "passive"))
      (node (ref "C133") (pin "1") (pinfunction "1_1") (pintype "passive"))
      (node (ref "C14") (pin "1") (pinfunction "1_1") (pintype "passive"))
      (node (ref "C15") (pin "1") (pinfunction "1_1") (pintype "passive"))
      (node (ref "C16") (pin "2") (pinfunction "2_2") (pintype "passive"))
      (node (ref "C17") (pin "2") (pinfunction "2_2") (pintype "passive"))
      (node (ref "C18") (pin "1") (pinfunction "1_1") (pintype "passive"))
      (node (ref "C19") (pin "1") (pinfunction "1_1") (pintype "passive"))
      (node (ref "C2") (pin "1") (pinfunction "1_1") (pintype "passive"))
      (node (ref "C20") (pin "1") (pinfunction "1_1") (pintype "passive"))
      (node (ref "C21") (pin "1") (pinfunction "1_1") (pintype "passive"))
      (node (ref "C22") (pin "2") (pinfunction "2_2") (pintype "passive"))
      (node (ref "C23") (pin "2") (pinfunction "2_2") (pintype "passive"))
      (node (ref "C24") (pin "1") (pinfunction "1_1") (pintype "passive"))
      (node (ref "C25") (pin "1") (pinfunction "1_1") (pintype "passive"))
      (node (ref "C26") (pin "2") (pinfunction "-_2") (pintype "passive"))
      (node (ref "C27") (pin "2") (pinfunction "-_2") (pintype "passive"))
      (node (ref "C28") (pin "2") (pinfunction "-_2") (pintype "passive"))
      (node (ref "C29") (pin "1") (pinfunction "1_1") (pintype "passive"))
      (node (ref "C3") (pin "1") (pinfunction "1_1") (pintype "passive"))
      (node (ref "C30") (pin "1") (pinfunction "1_1") (pintype "passive"))
      (node (ref "C31") (pin "1") (pinfunction "1_1") (pintype "passive"))
      (node (ref "C34") (pin "1") (pinfunction "1_1") (pintype "passive"))
      (node (ref "C35") (pin "2") (pinfunction "2_2") (pintype "passive"))
      (node (ref "C36") (pin "2") (pinfunction "2_2") (pintype "passive"))
      (node (ref "C38") (pin "1") (pinfunction "1_1") (pintype "passive"))
      (node (ref "C4") (pin "1") (pinfunction "1_1") (pintype "passive"))
      (node (ref "C40") (pin "2") (pinfunction "2_2") (pintype "passive"))
      (node (ref "C41") (pin "2") (pinfunction "2_2") (pintype "passive"))
      (node (ref "C42") (pin "1") (pinfunction "1_1") (pintype "passive"))
      (node (ref "C43") (pin "1") (pinfunction "1_1") (pintype "passive"))
      (node (ref "C44") (pin "1") (pinfunction "1_1") (pintype "passive"))
      (node (ref "C45") (pin "1") (pinfunction "1_1") (pintype "passive"))
      (node (ref "C47") (pin "1") (pinfunction "1_1") (pintype "passive"))
      (node (ref "C48") (pin "1") (pinfunction "1_1") (pintype "passive"))
      (node (ref "C49") (pin "2") (pinfunction "2_2") (pintype "passive"))
      (node (ref "C5") (pin "1") (pinfunction "1_1") (pintype "passive"))
      (node (ref "C50") (pin "2") (pinfunction "2_2") (pintype "passive"))
      (node (ref "C51") (pin "1") (pinfunction "1_1") (pintype "passive"))
      (node (ref "C53") (pin "2") (pinfunction "-_2") (pintype "passive"))
      (node (ref "C54") (pin "1") (pinfunction "1_1") (pintype "passive"))
      (node (ref "C55") (pin "1") (pinfunction "1_1") (pintype "passive"))
      (node (ref "C56") (pin "1") (pinfunction "1_1") (pintype "passive"))
      (node (ref "C57") (pin "1") (pinfunction "1_1") (pintype "passive"))
      (node (ref "C58") (pin "1") (pinfunction "1_1") (pintype "passive"))
      (node (ref "C59") (pin "1") (pinfunction "1_1") (pintype "passive"))
      (node (ref "C6") (pin "1") (pinfunction "1_1") (pintype "passive"))
      (node (ref "C66") (pin "1") (pinfunction "1_1") (pintype "passive"))
      (node (ref "C67") (pin "1") (pinfunction "1_1") (pintype "passive"))
      (node (ref "C68") (pin "2") (pinfunction "2_2") (pintype "passive"))
      (node (ref "C69") (pin "2") (pinfunction "2_2") (pintype "passive"))
      (node (ref "C7") (pin "1") (pinfunction "1_1") (pintype "passive"))
      (node (ref "C70") (pin "2") (pinfunction "2_2") (pintype "passive"))
      (node (ref "C71") (pin "2") (pinfunction "2_2") (pintype "passive"))
      (node (ref "C72") (pin "2") (pinfunction "2_2") (pintype "passive"))
      (node (ref "C73") (pin "1") (pinfunction "1_1") (pintype "passive"))
      (node (ref "C74") (pin "1") (pinfunction "1_1") (pintype "passive"))
      (node (ref "C75") (pin "2") (pinfunction "2_2") (pintype "passive"))
      (node (ref "C76") (pin "2") (pinfunction "2_2") (pintype "passive"))
      (node (ref "C77") (pin "2") (pinfunction "2_2") (pintype "passive"))
      (node (ref "C78") (pin "2") (pinfunction "-_2") (pintype "passive"))
      (node (ref "C79") (pin "2") (pinfunction "-_2") (pintype "passive"))
      (node (ref "C8") (pin "1") (pinfunction "1_1") (pintype "passive"))
      (node (ref "C80") (pin "2") (pinfunction "-_2") (pintype "passive"))
      (node (ref "C81") (pin "1") (pinfunction "1_1") (pintype "passive"))
      (node (ref "C82") (pin "1") (pinfunction "1_1") (pintype "passive"))
      (node (ref "C84") (pin "1") (pinfunction "1_1") (pintype "passive"))
      (node (ref "C85") (pin "2") (pinfunction "2_2") (pintype "passive"))
      (node (ref "C86") (pin "2") (pinfunction "2_2") (pintype "passive"))
      (node (ref "C88") (pin "2") (pinfunction "2_2") (pintype "passive"))
      (node (ref "C89") (pin "1") (pinfunction "1_1") (pintype "passive"))
      (node (ref "C9") (pin "1") (pinfunction "1_1") (pintype "passive"))
      (node (ref "C90") (pin "2") (pinfunction "-_2") (pintype "passive"))
      (node (ref "C91") (pin "2") (pinfunction "-_2") (pintype "passive"))
      (node (ref "C92") (pin "2") (pinfunction "-_2") (pintype "passive"))
      (node (ref "C93") (pin "2") (pinfunction "-_2") (pintype "passive"))
      (node (ref "C94") (pin "2") (pinfunction "-_2") (pintype "passive"))
      (node (ref "C95") (pin "1") (pinfunction "1_1") (pintype "passive"))
      (node (ref "C96") (pin "2") (pinfunction "2_2") (pintype "passive"))
      (node (ref "C97") (pin "2") (pinfunction "2_2") (pintype "passive"))
      (node (ref "C98") (pin "1") (pinfunction "1_1") (pintype "passive"))
      (node (ref "C99") (pin "1") (pinfunction "1_1") (pintype "passive"))
      (node (ref "CAL") (pin "2") (pinfunction "2_2") (pintype "passive"))
      (node (ref "D6") (pin "K") (pinfunction "K_K") (pintype "passive"))
      (node (ref "EMUL") (pin "1") (pinfunction "1_1") (pintype "passive"))
      (node (ref "Emulator") (pin "2") (pinfunction "2_2") (pintype "passive"))
      (node (ref "Emulator") (pin "3") (pinfunction "3_3") (pintype "passive"))
      (node (ref "Emulator") (pin "7") (pinfunction "7_7") (pintype "passive"))
      (node (ref "IC1") (pin "4") (pinfunction "-Vs_4") (pintype "power_in"))
      (node (ref "IC10") (pin "2") (pinfunction "GND_2") (pintype "power_in"))
      (node (ref "IC11") (pin "4") (pinfunction "GND_4") (pintype "passive"))
      (node (ref "IC12") (pin "4") (pinfunction "GND_4") (pintype "passive"))
      (node (ref "IC13") (pin "4") (pinfunction "-Vs_4") (pintype "power_in"))
      (node (ref "IC14") (pin "4") (pinfunction "GND_4") (pintype "passive"))
      (node (ref "IC15") (pin "14") (pinfunction "DGND_14") (pintype "power_in"))
      (node (ref "IC15") (pin "15") (pinfunction "DGND_15") (pintype "power_in"))
      (node (ref "IC15") (pin "16") (pinfunction "DGND_16") (pintype "power_in"))
      (node (ref "IC15") (pin "17") (pinfunction "DGND_17") (pintype "power_in"))
      (node (ref "IC15") (pin "18") (pinfunction "DGND_18") (pintype "power_in"))
      (node (ref "IC15") (pin "19") (pinfunction "DGND_19") (pintype "power_in"))
      (node (ref "IC15") (pin "2") (pinfunction "AGND_2") (pintype "power_in"))
      (node (ref "IC15") (pin "20") (pinfunction "DGND_20") (pintype "power_in"))
      (node (ref "IC15") (pin "21") (pinfunction "RSV2_21") (pintype "power_in"))
      (node (ref "IC15") (pin "22") (pinfunction "RSV1_22") (pintype "power_in"))
      (node (ref "IC15") (pin "25") (pinfunction "DGND_25") (pintype "power_in"))
      (node (ref "IC15") (pin "26") (pinfunction "DGND_26") (pintype "power_in"))
      (node (ref "IC15") (pin "3") (pinfunction "AGND_3") (pintype "power_in"))
      (node (ref "IC15") (pin "31") (pinfunction "DGND_31") (pintype "power_in"))
      (node (ref "IC15") (pin "47") (pinfunction "DGND_47") (pintype "power_in"))
      (node (ref "IC15") (pin "50") (pinfunction "DGND_50") (pintype "power_in"))
      (node (ref "IC15") (pin "51") (pinfunction "DGND_51") (pintype "power_in"))
      (node (ref "IC15") (pin "54") (pinfunction "AGND_54") (pintype "power_in"))
      (node (ref "IC15") (pin "56") (pinfunction "AGND_56") (pintype "power_in"))
      (node (ref "IC15") (pin "57") (pinfunction "AGND_57") (pintype "power_in"))
      (node (ref "IC15") (pin "6") (pinfunction "AGND_6") (pintype "power_in"))
      (node (ref "IC15") (pin "60") (pinfunction "VREFN_60") (pintype "power_in"))
      (node (ref "IC15") (pin "61") (pinfunction "VREFN_61") (pintype "power_in"))
      (node (ref "IC15") (pin "9") (pinfunction "AGND_9") (pintype "power_in"))
      (node (ref "IC16") (pin "2") (pinfunction "GND_2") (pintype "power_in"))
      (node (ref "IC17") (pin "4") (pinfunction "GND_4") (pintype "passive"))
      (node (ref "IC18") (pin "2") (pinfunction "GND_2") (pintype "passive"))
      (node (ref "IC2") (pin "4") (pinfunction "GND_4") (pintype "passive"))
      (node (ref "IC3") (pin "13") (pinfunction "AGND_13") (pintype "power_in"))
      (node (ref "IC3") (pin "4") (pinfunction "DGND_4") (pintype "power_in"))
      (node (ref "IC4") (pin "12") (pinfunction "GND_12") (pintype "power_in"))
      (node (ref "IC4") (pin "27") (pinfunction "GNG_27") (pintype "power_in"))
      (node (ref "IC4") (pin "3") (pinfunction "GNDA_3") (pintype "power_in"))
      (node (ref "IC4") (pin "39") (pinfunction "GND_39") (pintype "power_in"))
      (node (ref "IC4") (pin "55") (pinfunction "GND_55") (pintype "power_in"))
      (node (ref "IC5") (pin "3") (pinfunction "IN(+)_3") (pintype "input"))
      (node (ref "IC5") (pin "5") (pinfunction "IN(+)_5") (pintype "input"))
      (node (ref "IC6") (pin "1") (pinfunction "~{OE}_1") (pintype "input"))
      (node (ref "IC6") (pin "3") (pinfunction "GND_3") (pintype "power_in"))
      (node (ref "IC7") (pin "2") (pinfunction "Vocm_2") (pintype "input"))
      (node (ref "IC8") (pin "6") (pinfunction "GND_6") (pintype "passive"))
      (node (ref "IC9") (pin "2") (pinfunction "gnd1_2") (pintype "power_in"))
      (node (ref "IC9") (pin "8") (pinfunction "gnd1_8") (pintype "input"))
      (node (ref "JTAG") (pin "6") (pinfunction "GND_6") (pintype "passive"))
      (node (ref "L8") (pin "1") (pinfunction "1_1") (pintype "passive"))
      (node (ref "MIOC") (pin "1") (pinfunction "1_1") (pintype "passive"))
      (node (ref "OSC1") (pin "4") (pinfunction "GND_4") (pintype "power_in"))
      (node (ref "Output") (pin "5") (pinfunction "5_5") (pintype "passive"))
      (node (ref "PHOTODETECTOR") (pin "S") (pinfunction "S_S") (pintype "passive"))
      (node (ref "R32") (pin "1") (pinfunction "1_1") (pintype "passive"))
      (node (ref "R41") (pin "2") (pinfunction "2_2") (pintype "passive"))
      (node (ref "R63") (pin "1") (pinfunction "1_1") (pintype "passive"))
      (node (ref "R65") (pin "1") (pinfunction "1_1") (pintype "passive"))
      (node (ref "R66") (pin "1") (pinfunction "1_1") (pintype "passive"))
      (node (ref "R71") (pin "1") (pinfunction "1_1") (pintype "passive"))
      (node (ref "R73") (pin "1") (pinfunction "1_1") (pintype "passive"))
      (node (ref "R76") (pin "2") (pinfunction "2_2") (pintype "passive"))
      (node (ref "R8") (pin "1") (pinfunction "1_1") (pintype "passive"))
      (node (ref "RST") (pin "2") (pinfunction "2_2") (pintype "passive"))
      (node (ref "U1") (pin "4") (pinfunction "-Vs_4") (pintype "power_in"))
      (node (ref "U1") (pin "8") (pinfunction "~{EN}_8") (pintype "power_in"))
    )
    (net (code "44") (name "Net-(C26-+)") (class "Default")
      (node (ref "C26") (pin "1") (pinfunction "+_1") (pintype "passive"))
      (node (ref "IC2") (pin "6") (pinfunction "VOUT_6") (pintype "passive"))
      (node (ref "R9") (pin "1") (pinfunction "1_1") (pintype "passive"))
    )
    (net (code "45") (name "Net-(C27-+)") (class "Default")
      (node (ref "C27") (pin "1") (pinfunction "+_1") (pintype "passive"))
      (node (ref "IC2") (pin "5") (pinfunction "TRIM_5") (pintype "passive"))
    )
    (net (code "46") (name "Net-(C28-+)") (class "Default")
      (node (ref "C28") (pin "1") (pinfunction "+_1") (pintype "passive"))
      (node (ref "C29") (pin "2") (pinfunction "2_2") (pintype "passive"))
      (node (ref "IC1") (pin "3") (pinfunction "IN(+)_3") (pintype "input"))
      (node (ref "R9") (pin "2") (pinfunction "2_2") (pintype "passive"))
    )
    (net (code "47") (name "Net-(C53-+)") (class "Default")
      (node (ref "C53") (pin "1") (pinfunction "+_1") (pintype "passive"))
      (node (ref "C54") (pin "2") (pinfunction "2_2") (pintype "passive"))
      (node (ref "IC8") (pin "4") (pinfunction "VREF_4") (pintype "passive"))
      (node (ref "R38") (pin "1") (pinfunction "1_1") (pintype "passive"))
      (node (ref "R42") (pin "1") (pinfunction "1_1") (pintype "passive"))
      (node (ref "R46") (pin "1") (pinfunction "1_1") (pintype "passive"))
    )
    (net (code "48") (name "Net-(C66-Pad2)") (class "Default")
      (node (ref "C66") (pin "2") (pinfunction "2_2") (pintype "passive"))
      (node (ref "C67") (pin "2") (pinfunction "2_2") (pintype "passive"))
      (node (ref "IC15") (pin "58") (pinfunction "AVDD_58") (pintype "power_in"))
      (node (ref "L5") (pin "2") (pinfunction "2_2") (pintype "passive"))
    )
    (net (code "49") (name "Net-(C70-Pad1)") (class "Default")
      (node (ref "C70") (pin "1") (pinfunction "1_1") (pintype "passive"))
      (node (ref "R48") (pin "2") (pinfunction "2_2") (pintype "passive"))
      (node (ref "R49") (pin "1") (pinfunction "1_1") (pintype "passive"))
    )
    (net (code "50") (name "Net-(C76-Pad1)") (class "Default")
      (node (ref "C76") (pin "1") (pinfunction "1_1") (pintype "passive"))
      (node (ref "C77") (pin "1") (pinfunction "1_1") (pintype "passive"))
      (node (ref "IC15") (pin "48") (pinfunction "DVDD_48") (pintype "power_in"))
      (node (ref "IC15") (pin "49") (pinfunction "DVDD_49") (pintype "power_in"))
      (node (ref "IC15") (pin "52") (pinfunction "DVDD_52") (pintype "power_in"))
      (node (ref "L6") (pin "1") (pinfunction "1_1") (pintype "passive"))
    )
    (net (code "51") (name "Net-(C78-+)") (class "Default")
      (node (ref "C78") (pin "1") (pinfunction "+_1") (pintype "passive"))
      (node (ref "C79") (pin "1") (pinfunction "+_1") (pintype "passive"))
      (node (ref "C80") (pin "1") (pinfunction "+_1") (pintype "passive"))
      (node (ref "C84") (pin "2") (pinfunction "2_2") (pintype "passive"))
      (node (ref "IC15") (pin "63") (pinfunction "VREFP_63") (pintype "power_in"))
      (node (ref "IC15") (pin "64") (pinfunction "VREFP_64") (pintype "power_in"))
      (node (ref "R47") (pin "2") (pinfunction "2_2") (pintype "passive"))
      (node (ref "R52") (pin "2") (pinfunction "2_2") (pintype "passive"))
    )
    (net (code "52") (name "Net-(C90-+)") (class "Default")
      (node (ref "C90") (pin "1") (pinfunction "+_1") (pintype "passive"))
      (node (ref "IC12") (pin "6") (pinfunction "VOUT_6") (pintype "passive"))
      (node (ref "R53") (pin "1") (pinfunction "1_1") (pintype "passive"))
    )
    (net (code "53") (name "Net-(C92-+)") (class "Default")
      (node (ref "C92") (pin "1") (pinfunction "+_1") (pintype "passive"))
      (node (ref "IC12") (pin "5") (pinfunction "TRIM_5") (pintype "passive"))
    )
    (net (code "54") (name "Net-(C93-+)") (class "Default")
      (node (ref "C93") (pin "1") (pinfunction "+_1") (pintype "passive"))
      (node (ref "C94") (pin "1") (pinfunction "+_1") (pintype "passive"))
      (node (ref "C95") (pin "2") (pinfunction "2_2") (pintype "passive"))
      (node (ref "R53") (pin "2") (pinfunction "2_2") (pintype "passive"))
      (node (ref "U1") (pin "3") (pinfunction "IN(+)_3") (pintype "input"))
    )
    (net (code "55") (name "Net-(C113-Pad1)") (class "Default")
      (node (ref "C113") (pin "1") (pinfunction "1_1") (pintype "passive"))
      (node (ref "R67") (pin "2") (pinfunction "2_2") (pintype "passive"))
      (node (ref "R68") (pin "1") (pinfunction "1_1") (pintype "passive"))
    )
    (net (code "56") (name "Net-(C115-Pad1)") (class "Default")
      (node (ref "C115") (pin "1") (pinfunction "1_1") (pintype "passive"))
      (node (ref "C125") (pin "2") (pinfunction "2_2") (pintype "passive"))
    )
    (net (code "57") (name "Net-(C124-Pad2)") (class "Default")
      (node (ref "C124") (pin "2") (pinfunction "2_2") (pintype "passive"))
      (node (ref "C83") (pin "1") (pinfunction "1_1") (pintype "passive"))
    )
    (net (code "58") (name "Net-(D1-PadK)") (class "Default")
      (node (ref "D1") (pin "K") (pinfunction "K_K") (pintype "passive"))
      (node (ref "R16") (pin "2") (pinfunction "2_2") (pintype "passive"))
    )
    (net (code "59") (name "Net-(D2-PadK)") (class "Default")
      (node (ref "D2") (pin "K") (pinfunction "K_K") (pintype "passive"))
      (node (ref "R17") (pin "2") (pinfunction "2_2") (pintype "passive"))
    )
    (net (code "60") (name "Net-(D6-a)") (class "Default")
      (node (ref "D6") (pin "A") (pinfunction "a_A") (pintype "passive"))
      (node (ref "R58") (pin "1") (pinfunction "1_1") (pintype "passive"))
    )
    (net (code "61") (name "Net-(EMUL-Pad2)") (class "Default")
      (node (ref "EMUL") (pin "2") (pinfunction "2_2") (pintype "passive"))
      (node (ref "R56") (pin "2") (pinfunction "2_2") (pintype "passive"))
    )
    (net (code "62") (name "Net-(EMUL-Pad3)") (class "Default")
      (node (ref "EMUL") (pin "3") (pinfunction "3_3") (pintype "passive"))
      (node (ref "R54") (pin "1") (pinfunction "1_1") (pintype "passive"))
    )
    (net (code "63") (name "Net-(IC1A-IN(-))") (class "Default")
      (node (ref "C15") (pin "2") (pinfunction "2_2") (pintype "passive"))
      (node (ref "C18") (pin "2") (pinfunction "2_2") (pintype "passive"))
      (node (ref "C32") (pin "2") (pinfunction "2_2") (pintype "passive"))
      (node (ref "IC1") (pin "1") (pinfunction "OUT_1") (pintype "output"))
      (node (ref "IC1") (pin "2") (pinfunction "IN(-)_2") (pintype "input"))
      (node (ref "IC3") (pin "12") (pinfunction "Vref_12") (pintype "power_in"))
      (node (ref "R14") (pin "2") (pinfunction "2_2") (pintype "passive"))
    )
    (net (code "64") (name "Net-(IC1B-IN(+))") (class "Default")
      (node (ref "IC1") (pin "5") (pinfunction "IN(+)_5") (pintype "input"))
      (node (ref "R13") (pin "1") (pinfunction "1_1") (pintype "passive"))
      (node (ref "R14") (pin "1") (pinfunction "1_1") (pintype "passive"))
    )
    (net (code "65") (name "Net-(IC1B-IN(-))") (class "Default")
      (node (ref "C62") (pin "2") (pinfunction "2_2") (pintype "passive"))
      (node (ref "IC1") (pin "6") (pinfunction "IN(-)_6") (pintype "input"))
      (node (ref "R46") (pin "2") (pinfunction "2_2") (pintype "passive"))
    )
    (net (code "66") (name "Net-(IC1B-OUT)") (class "Default")
      (node (ref "C62") (pin "1") (pinfunction "1_1") (pintype "passive"))
      (node (ref "IC1") (pin "7") (pinfunction "OUT_7") (pintype "output"))
      (node (ref "R42") (pin "2") (pinfunction "2_2") (pintype "passive"))
    )
    (net (code "67") (name "Net-(IC3-C1)") (class "Default")
      (node (ref "C32") (pin "1") (pinfunction "1_1") (pintype "passive"))
      (node (ref "IC3") (pin "9") (pinfunction "C1_9") (pintype "power_in"))
    )
    (net (code "68") (name "Net-(IC3-C2)") (class "Default")
      (node (ref "C33") (pin "1") (pinfunction "1_1") (pintype "passive"))
      (node (ref "IC3") (pin "10") (pinfunction "C2_10") (pintype "tri_state"))
    )
    (net (code "69") (name "Net-(IC3-DVdd)") (class "Default")
      (node (ref "C16") (pin "1") (pinfunction "1_1") (pintype "passive"))
      (node (ref "C17") (pin "1") (pinfunction "1_1") (pintype "passive"))
      (node (ref "IC3") (pin "1") (pinfunction "DVdd_1") (pintype "power_in"))
      (node (ref "L2") (pin "2") (pinfunction "2_2") (pintype "passive"))
    )
    (net (code "70") (name "Net-(IC3-SCLK)") (class "Default")
      (node (ref "IC3") (pin "16") (pinfunction "SCLK_16") (pintype "power_in"))
      (node (ref "R7") (pin "1") (pinfunction "1_1") (pintype "passive"))
    )
    (net (code "71") (name "Net-(IC3-SDIO)") (class "Default")
      (node (ref "IC3") (pin "15") (pinfunction "SDIO_15") (pintype "power_in"))
      (node (ref "R10") (pin "1") (pinfunction "1_1") (pintype "passive"))
    )
    (net (code "72") (name "Net-(IC3-Vout)") (class "Default")
      (node (ref "C33") (pin "2") (pinfunction "2_2") (pintype "passive"))
      (node (ref "IC3") (pin "11") (pinfunction "Vout_11") (pintype "tri_state"))
      (node (ref "R13") (pin "2") (pinfunction "2_2") (pintype "passive"))
    )
    (net (code "73") (name "Net-(IC3-Xin)") (class "Default")
      (node (ref "IC3") (pin "3") (pinfunction "Xin_3") (pintype "power_in"))
      (node (ref "R11") (pin "1") (pinfunction "1_1") (pintype "passive"))
    )
    (net (code "74") (name "Net-(IC3-~{CS})") (class "Default")
      (node (ref "IC3") (pin "14") (pinfunction "~{CS}_14") (pintype "tri_state"))
      (node (ref "R12") (pin "1") (pinfunction "1_1") (pintype "passive"))
    )
    (net (code "75") (name "Net-(IC4-PA2{slash}SSI0Clk)") (class "Default")
      (node (ref "IC4") (pin "19") (pinfunction "PA2/SSI0Clk_19") (pintype "bidirectional"))
      (node (ref "R24") (pin "2") (pinfunction "2_2") (pintype "passive"))
    )
    (net (code "76") (name "Net-(IC4-PA4{slash}SSI0Rx)") (class "Default")
      (node (ref "IC4") (pin "21") (pinfunction "PA4/SSI0Rx_21") (pintype "bidirectional"))
      (node (ref "R25") (pin "2") (pinfunction "2_2") (pintype "passive"))
    )
    (net (code "77") (name "Net-(IC4-PA5{slash}SSI0Tx)") (class "Default")
      (node (ref "IC4") (pin "22") (pinfunction "PA5/SSI0Tx_22") (pintype "bidirectional"))
      (node (ref "R26") (pin "2") (pinfunction "2_2") (pintype "passive"))
    )
    (net (code "78") (name "Net-(IC4-PA6)") (class "Default")
      (node (ref "IC4") (pin "23") (pinfunction "PA6_23") (pintype "bidirectional"))
      (node (ref "R27") (pin "2") (pinfunction "2_2") (pintype "passive"))
    )
    (net (code "79") (name "Net-(IC4-PB0{slash}USB0ID)") (class "Default")
      (node (ref "CAL") (pin "1") (pinfunction "1_1") (pintype "passive"))
      (node (ref "IC4") (pin "45") (pinfunction "PB0/USB0ID_45") (pintype "bidirectional"))
      (node (ref "R3") (pin "2") (pinfunction "2_2") (pintype "passive"))
    )
    (net (code "80") (name "Net-(IC4-PB3{slash}I2C0SDA)") (class "Default")
      (node (ref "IC4") (pin "48") (pinfunction "PB3/I2C0SDA_48") (pintype "bidirectional"))
      (node (ref "R6") (pin "2") (pinfunction "2_2") (pintype "passive"))
    )
    (net (code "81") (name "Net-(IC4-PC4)") (class "Default")
      (node (ref "IC4") (pin "16") (pinfunction "PC4_16") (pintype "bidirectional"))
      (node (ref "R17") (pin "1") (pinfunction "1_1") (pintype "passive"))
    )
    (net (code "82") (name "Net-(IC4-PC5)") (class "Default")
      (node (ref "IC4") (pin "15") (pinfunction "PC5_15") (pintype "bidirectional"))
      (node (ref "IC6") (pin "2") (pinfunction "A_2") (pintype "input"))
    )
    (net (code "83") (name "Net-(IC4-PC6)") (class "Default")
      (node (ref "IC4") (pin "14") (pinfunction "PC6_14") (pintype "bidirectional"))
      (node (ref "R16") (pin "1") (pinfunction "1_1") (pintype "passive"))
    )
    (net (code "84") (name "Net-(IC4-PF0)") (class "Default")
      (node (ref "IC4") (pin "28") (pinfunction "PF0_28") (pintype "bidirectional"))
      (node (ref "R28") (pin "2") (pinfunction "2_2") (pintype "passive"))
    )
    (net (code "85") (name "Net-(IC4-VDDA)") (class "Default")
      (node (ref "C19") (pin "2") (pinfunction "2_2") (pintype "passive"))
      (node (ref "IC4") (pin "2") (pinfunction "VDDA_2") (pintype "power_in"))
      (node (ref "L1") (pin "2") (pinfunction "2_2") (pintype "passive"))
    )
    (net (code "86") (name "Net-(IC5A-IN(-))") (class "Default")
      (node (ref "C46") (pin "2") (pinfunction "2_2") (pintype "passive"))
      (node (ref "IC5") (pin "2") (pinfunction "IN(-)_2") (pintype "input"))
      (node (ref "R18") (pin "1") (pinfunction "1_1") (pintype "passive"))
      (node (ref "R37") (pin "2") (pinfunction "2_2") (pintype "passive"))
      (node (ref "R38") (pin "2") (pinfunction "2_2") (pintype "passive"))
    )
    (net (code "87") (name "Net-(IC5A-OUT)") (class "Default")
      (node (ref "C46") (pin "1") (pinfunction "1_1") (pintype "passive"))
      (node (ref "IC5") (pin "1") (pinfunction "OUT_1") (pintype "output"))
      (node (ref "R22") (pin "2") (pinfunction "2_2") (pintype "passive"))
      (node (ref "R37") (pin "1") (pinfunction "1_1") (pintype "passive"))
    )
    (net (code "88") (name "Net-(IC5B-IN(-))") (class "Default")
      (node (ref "C37") (pin "2") (pinfunction "2_2") (pintype "passive"))
      (node (ref "IC5") (pin "6") (pinfunction "IN(-)_6") (pintype "input"))
      (node (ref "IC8") (pin "5") (pinfunction "IOUT_5") (pintype "passive"))
    )
    (net (code "89") (name "Net-(IC5B-OUT)") (class "Default")
      (node (ref "C37") (pin "1") (pinfunction "1_1") (pintype "passive"))
      (node (ref "IC5") (pin "7") (pinfunction "OUT_7") (pintype "output"))
      (node (ref "IC8") (pin "3") (pinfunction "RFB_3") (pintype "passive"))
      (node (ref "R18") (pin "2") (pinfunction "2_2") (pintype "passive"))
    )
    (net (code "90") (name "Net-(IC6-Vcc)") (class "Default")
      (node (ref "C47") (pin "2") (pinfunction "2_2") (pintype "passive"))
      (node (ref "IC6") (pin "5") (pinfunction "Vcc_5") (pintype "power_in"))
      (node (ref "R39") (pin "2") (pinfunction "2_2") (pintype "passive"))
    )
    (net (code "91") (name "Net-(IC6-Y)") (class "Default")
      (node (ref "IC6") (pin "4") (pinfunction "Y_4") (pintype "output"))
      (node (ref "R21") (pin "1") (pinfunction "1_1") (pintype "passive"))
    )
    (net (code "92") (name "Net-(IC7-Vin+)") (class "Default")
      (node (ref "C52") (pin "1") (pinfunction "1_1") (pintype "passive"))
      (node (ref "IC7") (pin "8") (pinfunction "Vin+_8") (pintype "input"))
      (node (ref "R41") (pin "1") (pinfunction "1_1") (pintype "passive"))
      (node (ref "R43") (pin "2") (pinfunction "2_2") (pintype "passive"))
    )
    (net (code "93") (name "Net-(IC7-Vin-)") (class "Default")
      (node (ref "910") (pin "2") (pinfunction "2_2") (pintype "passive"))
      (node (ref "C39") (pin "1") (pinfunction "1_1") (pintype "passive"))
      (node (ref "IC7") (pin "1") (pinfunction "Vin-_1") (pintype "input"))
      (node (ref "R22") (pin "1") (pinfunction "1_1") (pintype "passive"))
    )
    (net (code "94") (name "Net-(IC7-Vout+)") (class "Default")
      (node (ref "910") (pin "1") (pinfunction "1_1") (pintype "passive"))
      (node (ref "C39") (pin "2") (pinfunction "2_2") (pintype "passive"))
      (node (ref "IC7") (pin "4") (pinfunction "Vout+_4") (pintype "output"))
      (node (ref "R31") (pin "2") (pinfunction "2_2") (pintype "passive"))
    )
    (net (code "95") (name "Net-(IC7-Vout-)") (class "Default")
      (node (ref "C52") (pin "2") (pinfunction "2_2") (pintype "passive"))
      (node (ref "IC7") (pin "5") (pinfunction "Vout-_5") (pintype "output"))
      (node (ref "R36") (pin "2") (pinfunction "2_2") (pintype "passive"))
      (node (ref "R43") (pin "1") (pinfunction "1_1") (pintype "passive"))
    )
    (net (code "96") (name "Net-(IC7-{slash}PD)") (class "Default")
      (node (ref "IC7") (pin "7") (pinfunction "/PD_7") (pintype "input"))
      (node (ref "R44") (pin "1") (pinfunction "1_1") (pintype "passive"))
      (node (ref "R45") (pin "2") (pinfunction "2_2") (pintype "passive"))
    )
    (net (code "97") (name "Net-(IC8-CLK)") (class "Default")
      (node (ref "IC8") (pin "1") (pinfunction "CLK_1") (pintype "passive"))
      (node (ref "R20") (pin "2") (pinfunction "2_2") (pintype "passive"))
    )
    (net (code "98") (name "Net-(IC8-SDI)") (class "Default")
      (node (ref "IC8") (pin "2") (pinfunction "SDI_2") (pintype "passive"))
      (node (ref "R23") (pin "2") (pinfunction "2_2") (pintype "passive"))
    )
    (net (code "99") (name "Net-(IC8-VDD)") (class "Default")
      (node (ref "C44") (pin "2") (pinfunction "2_2") (pintype "passive"))
      (node (ref "C45") (pin "2") (pinfunction "2_2") (pintype "passive"))
      (node (ref "IC8") (pin "7") (pinfunction "VDD_7") (pintype "passive"))
      (node (ref "L3") (pin "2") (pinfunction "2_2") (pintype "passive"))
    )
    (net (code "100") (name "Net-(IC9-PV)") (class "Default")
      (node (ref "IC9") (pin "7") (pinfunction "PV_7") (pintype "input"))
      (node (ref "R40") (pin "1") (pinfunction "1_1") (pintype "passive"))
    )
    (net (code "101") (name "Net-(IC11-C+)") (class "Default")
      (node (ref "C64") (pin "2") (pinfunction "2_2") (pintype "passive"))
      (node (ref "IC11") (pin "5") (pinfunction "C+_5") (pintype "passive"))
    )
    (net (code "102") (name "Net-(IC11-C-)") (class "Default")
      (node (ref "C64") (pin "1") (pinfunction "1_1") (pintype "passive"))
      (node (ref "IC11") (pin "3") (pinfunction "C-_3") (pintype "passive"))
    )
    (net (code "103") (name "Net-(IC11-OUT)") (class "Default")
      (node (ref "C74") (pin "2") (pinfunction "2_2") (pintype "passive"))
      (node (ref "IC11") (pin "1") (pinfunction "OUT_1") (pintype "passive"))
      (node (ref "R50") (pin "1") (pinfunction "1_1") (pintype "passive"))
    )
    (net (code "104") (name "Net-(IC13A-IN(-))") (class "Default")
      (node (ref "C83") (pin "2") (pinfunction "2_2") (pintype "passive"))
      (node (ref "IC13") (pin "2") (pinfunction "IN(-)_2") (pintype "input"))
      (node (ref "PHOTODETECTOR") (pin "K") (pinfunction "K_K") (pintype "output"))
      (node (ref "R48") (pin "1") (pinfunction "1_1") (pintype "passive"))
      (node (ref "R51") (pin "1") (pinfunction "1_1") (pintype "passive"))
      (node (ref "R54") (pin "2") (pinfunction "2_2") (pintype "passive"))
    )
    (net (code "105") (name "Net-(IC13A-OUT)") (class "Default")
      (node (ref "C124") (pin "1") (pinfunction "1_1") (pintype "passive"))
      (node (ref "IC13") (pin "1") (pinfunction "OUT_1") (pintype "output"))
      (node (ref "R49") (pin "2") (pinfunction "2_2") (pintype "passive"))
      (node (ref "R51") (pin "2") (pinfunction "2_2") (pintype "passive"))
      (node (ref "R69") (pin "1") (pinfunction "1_1") (pintype "passive"))
    )
    (net (code "106") (name "Net-(IC13B-IN(-))") (class "Default")
      (node (ref "C115") (pin "2") (pinfunction "2_2") (pintype "passive"))
      (node (ref "IC13") (pin "6") (pinfunction "IN(-)_6") (pintype "input"))
      (node (ref "PHOTODETECTOR") (pin "A") (pinfunction "A_A") (pintype "input"))
      (node (ref "R56") (pin "1") (pinfunction "1_1") (pintype "passive"))
      (node (ref "R67") (pin "1") (pinfunction "1_1") (pintype "passive"))
      (node (ref "R74") (pin "1") (pinfunction "1_1") (pintype "passive"))
    )
    (net (code "107") (name "Net-(IC13B-OUT)") (class "Default")
      (node (ref "C125") (pin "1") (pinfunction "1_1") (pintype "passive"))
      (node (ref "IC13") (pin "7") (pinfunction "OUT_7") (pintype "output"))
      (node (ref "R60") (pin "1") (pinfunction "1_1") (pintype "passive"))
      (node (ref "R68") (pin "2") (pinfunction "2_2") (pintype "passive"))
      (node (ref "R74") (pin "2") (pinfunction "2_2") (pintype "passive"))
    )
    (net (code "108") (name "Net-(IC14-C+)") (class "Default")
      (node (ref "C87") (pin "2") (pinfunction "2_2") (pintype "passive"))
      (node (ref "IC14") (pin "5") (pinfunction "C+_5") (pintype "passive"))
    )
    (net (code "109") (name "Net-(IC14-C-)") (class "Default")
      (node (ref "C87") (pin "1") (pinfunction "1_1") (pintype "passive"))
      (node (ref "IC14") (pin "3") (pinfunction "C-_3") (pintype "passive"))
    )
    (net (code "110") (name "Net-(IC14-OUT)") (class "Default")
      (node (ref "C99") (pin "2") (pinfunction "2_2") (pintype "passive"))
      (node (ref "IC14") (pin "1") (pinfunction "OUT_1") (pintype "passive"))
      (node (ref "R55") (pin "1") (pinfunction "1_1") (pintype "passive"))
    )
    (net (code "111") (name "Net-(IC15-AINN)") (class "Default")
      (node (ref "C109") (pin "1") (pinfunction "1_1") (pintype "passive"))
      (node (ref "C111") (pin "1") (pinfunction "1_1") (pintype "passive"))
      (node (ref "IC15") (pin "4") (pinfunction "AINN_4") (pintype "input"))
      (node (ref "R60") (pin "2") (pinfunction "2_2") (pintype "passive"))
    )
    (net (code "112") (name "Net-(IC15-AINP)") (class "Default")
      (node (ref "C111") (pin "2") (pinfunction "2_2") (pintype "passive"))
      (node (ref "C114") (pin "1") (pinfunction "1_1") (pintype "passive"))
      (node (ref "IC15") (pin "5") (pinfunction "AINP_5") (pintype "input"))
      (node (ref "R69") (pin "2") (pinfunction "2_2") (pintype "passive"))
    )
    (net (code "113") (name "Net-(IC15-CAP1)") (class "Default")
      (node (ref "C82") (pin "2") (pinfunction "2_2") (pintype "passive"))
      (node (ref "IC15") (pin "59") (pinfunction "CAP1_59") (pintype "power_in"))
    )
    (net (code "114") (name "Net-(IC15-CAP2)") (class "Default")
      (node (ref "C81") (pin "2") (pinfunction "2_2") (pintype "passive"))
      (node (ref "IC15") (pin "62") (pinfunction "CAP2_62") (pintype "power_in"))
    )
    (net (code "115") (name "Net-(IC15-DRATE[0])") (class "Default")
      (node (ref "IC15") (pin "36") (pinfunction "DRATE[0]_36") (pintype "power_in"))
      (node (ref "R62") (pin "2") (pinfunction "2_2") (pintype "passive"))
      (node (ref "R63") (pin "2") (pinfunction "2_2") (pintype "passive"))
    )
    (net (code "116") (name "Net-(IC15-DRATE[1])") (class "Default")
      (node (ref "IC15") (pin "35") (pinfunction "DRATE[1]_35") (pintype "power_in"))
      (node (ref "R64") (pin "2") (pinfunction "2_2") (pintype "passive"))
      (node (ref "R65") (pin "2") (pinfunction "2_2") (pintype "passive"))
    )
    (net (code "117") (name "Net-(IC15-FPATH)") (class "Default")
      (node (ref "IC15") (pin "33") (pinfunction "FPATH_33") (pintype "power_in"))
      (node (ref "R70") (pin "2") (pinfunction "2_2") (pintype "passive"))
      (node (ref "R71") (pin "2") (pinfunction "2_2") (pintype "passive"))
    )
    (net (code "118") (name "Net-(IC15-LL_CONFIG)") (class "Default")
      (node (ref "IC15") (pin "32") (pinfunction "LL_CONFIG_32") (pintype "power_in"))
      (node (ref "R72") (pin "2") (pinfunction "2_2") (pintype "passive"))
      (node (ref "R73") (pin "2") (pinfunction "2_2") (pintype "passive"))
    )
    (net (code "119") (name "Net-(IC15-RBIAS)") (class "Default")
      (node (ref "IC15") (pin "8") (pinfunction "RBIAS_8") (pintype "power_in"))
      (node (ref "R66") (pin "2") (pinfunction "2_2") (pintype "passive"))
    )
    (net (code "120") (name "Net-(IC15-SCLK)") (class "Default")
      (node (ref "IC15") (pin "42") (pinfunction "SCLK_42") (pintype "power_in"))
      (node (ref "R57") (pin "1") (pinfunction "1_1") (pintype "passive"))
    )
    (net (code "121") (name "Net-(IC15-SCLK_SEL)") (class "Default")
      (node (ref "C110") (pin "1") (pinfunction "1_1") (pintype "passive"))
      (node (ref "C131") (pin "2") (pinfunction "2_2") (pintype "passive"))
      (node (ref "IC15") (pin "29") (pinfunction "SCLK_SEL_29") (pintype "power_in"))
      (node (ref "IC15") (pin "30") (pinfunction "~{LVDS}_30") (pintype "power_in"))
      (node (ref "IC15") (pin "34") (pinfunction "DVDD_34") (pintype "power_in"))
      (node (ref "L10") (pin "1") (pinfunction "1_1") (pintype "passive"))
      (node (ref "R62") (pin "1") (pinfunction "1_1") (pintype "passive"))
      (node (ref "R64") (pin "1") (pinfunction "1_1") (pintype "passive"))
      (node (ref "R70") (pin "1") (pinfunction "1_1") (pintype "passive"))
      (node (ref "R72") (pin "1") (pinfunction "1_1") (pintype "passive"))
    )
    (net (code "122") (name "Net-(IC15-START)") (class "Default")
      (node (ref "IC15") (pin "37") (pinfunction "START_37") (pintype "power_in"))
      (node (ref "R61") (pin "1") (pinfunction "1_1") (pintype "passive"))
    )
    (net (code "123") (name "Net-(IC15-VCM)") (class "Default")
      (node (ref "C112") (pin "1") (pinfunction "1_1") (pintype "passive"))
      (node (ref "IC15") (pin "13") (pinfunction "VCM_13") (pintype "power_in"))
    )
    (net (code "124") (name "Net-(IC15-~{CS})") (class "Default")
      (node (ref "IC15") (pin "38") (pinfunction "~{CS}_38") (pintype "power_in"))
      (node (ref "R59") (pin "1") (pinfunction "1_1") (pintype "passive"))
    )
    (net (code "125") (name "Net-(IC15-~{PDWN})") (class "Default")
      (node (ref "C116") (pin "1") (pinfunction "1_1") (pintype "passive"))
      (node (ref "C117") (pin "1") (pinfunction "1_1") (pintype "passive"))
      (node (ref "C118") (pin "1") (pinfunction "1_1") (pintype "passive"))
      (node (ref "IC15") (pin "23") (pinfunction "DVDD_23") (pintype "power_in"))
      (node (ref "IC15") (pin "24") (pinfunction "DVDD_24") (pintype "power_in"))
      (node (ref "IC15") (pin "27") (pinfunction "DVDD_27") (pintype "power_in"))
      (node (ref "IC15") (pin "28") (pinfunction "~{PDWN}_28") (pintype "power_in"))
      (node (ref "L9") (pin "2") (pinfunction "2_2") (pintype "passive"))
    )
    (net (code "126") (name "Net-(IC17-TRIM)") (class "Default")
      (node (ref "C121") (pin "1") (pinfunction "1_1") (pintype "passive"))
      (node (ref "IC17") (pin "5") (pinfunction "TRIM_5") (pintype "passive"))
    )
    (net (code "127") (name "Net-(IC17-VOUT)") (class "Default")
      (node (ref "C122") (pin "2") (pinfunction "2_2") (pintype "passive"))
      (node (ref "C123") (pin "2") (pinfunction "2_2") (pintype "passive"))
      (node (ref "IC17") (pin "6") (pinfunction "VOUT_6") (pintype "passive"))
      (node (ref "R75") (pin "2") (pinfunction "2_2") (pintype "passive"))
    )
    (net (code "128") (name "Net-(IC18-NR)") (class "Default")
      (node (ref "C129") (pin "2") (pinfunction "2_2") (pintype "passive"))
      (node (ref "IC18") (pin "4") (pinfunction "NR_4") (pintype "passive"))
    )
    (net (code "129") (name "Net-(L4-Pad2)") (class "Default")
      (node (ref "L4") (pin "2") (pinfunction "2_2") (pintype "passive"))
      (node (ref "R39") (pin "1") (pinfunction "1_1") (pintype "passive"))
    )
    (net (code "130") (name "Net-(L7-Pad2)") (class "Default")
      (node (ref "L7") (pin "2") (pinfunction "2_2") (pintype "passive"))
      (node (ref "POWER") (pin "1") (pinfunction "1_1") (pintype "passive"))
    )
    (net (code "131") (name "Net-(L8-Pad2)") (class "Default")
      (node (ref "L8") (pin "2") (pinfunction "2_2") (pintype "passive"))
      (node (ref "POWER") (pin "2") (pinfunction "2_2") (pintype "passive"))
    )
    (net (code "132") (name "Net-(MIOC-Pad2)") (class "Default")
      (node (ref "MIOC") (pin "2") (pinfunction "2_2") (pintype "passive"))
      (node (ref "R36") (pin "1") (pinfunction "1_1") (pintype "passive"))
    )
    (net (code "133") (name "Net-(MIOC-Pad3)") (class "Default")
      (node (ref "MIOC") (pin "3") (pinfunction "3_3") (pintype "passive"))
      (node (ref "R31") (pin "1") (pinfunction "1_1") (pintype "passive"))
    )
    (net (code "134") (name "Net-(OSC1-OUT)") (class "Default")
      (node (ref "C25") (pin "2") (pinfunction "2_2") (pintype "passive"))
      (node (ref "OSC1") (pin "5") (pinfunction "OUT_5") (pintype "output"))
      (node (ref "R1") (pin "1") (pinfunction "1_1") (pintype "passive"))
      (node (ref "R5") (pin "1") (pinfunction "1_1") (pintype "passive"))
    )
    (net (code "135") (name "Net-(OSC1-VCC)") (class "Default")
      (node (ref "C21") (pin "2") (pinfunction "2_2") (pintype "passive"))
      (node (ref "C22") (pin "1") (pinfunction "1_1") (pintype "passive"))
      (node (ref "OSC1") (pin "9") (pinfunction "VCC_9") (pintype "power_in"))
      (node (ref "R2") (pin "1") (pinfunction "1_1") (pintype "passive"))
      (node (ref "R4") (pin "1") (pinfunction "1_1") (pintype "passive"))
    )
    (net (code "136") (name "Net-(R34-Pad2)") (class "Default")
      (node (ref "R34") (pin "2") (pinfunction "2_2") (pintype "passive"))
      (node (ref "RX") (pin "K") (pinfunction "K_K") (pintype "passive"))
    )
    (net (code "137") (name "Net-(R35-Pad2)") (class "Default")
      (node (ref "R35") (pin "2") (pinfunction "2_2") (pintype "passive"))
      (node (ref "TX") (pin "K") (pinfunction "K_K") (pintype "passive"))
    )
    (net (code "138") (name "Net-(U1-IN(-))") (class "Default")
      (node (ref "C65") (pin "1") (pinfunction "1_1") (pintype "passive"))
      (node (ref "R47") (pin "1") (pinfunction "1_1") (pintype "passive"))
      (node (ref "U1") (pin "2") (pinfunction "IN(-)_2") (pintype "input"))
    )
    (net (code "139") (name "Net-(U1-OUT)") (class "Default")
      (node (ref "C65") (pin "2") (pinfunction "2_2") (pintype "passive"))
      (node (ref "R52") (pin "1") (pinfunction "1_1") (pintype "passive"))
      (node (ref "U1") (pin "6") (pinfunction "OUT_6") (pintype "output"))
    )
    (net (code "140") (name "unconnected-(IC1B-+Vs-Pad8)") (class "Default")
      (node (ref "IC1") (pin "8") (pinfunction "+Vs_8") (pintype "power_in"))
    )
    (net (code "141") (name "unconnected-(IC1B--Vs-Pad4)") (class "Default")
      (node (ref "IC1") (pin "4") (pinfunction "-Vs_4") (pintype "power_in"))
    )
    (net (code "142") (name "unconnected-(IC2-NC-Pad1)") (class "Default")
      (node (ref "IC2") (pin "1") (pinfunction "NC_1") (pintype "passive"))
    )
    (net (code "143") (name "unconnected-(IC2-NC-Pad3)") (class "Default")
      (node (ref "IC2") (pin "3") (pinfunction "NC_3") (pintype "passive"))
    )
    (net (code "144") (name "unconnected-(IC2-NC-Pad7)") (class "Default")
      (node (ref "IC2") (pin "7") (pinfunction "NC_7") (pintype "passive"))
    )
    (net (code "145") (name "unconnected-(IC2-NC-Pad8)") (class "Default")
      (node (ref "IC2") (pin "8") (pinfunction "NC_8") (pintype "passive"))
    )
    (net (code "146") (name "unconnected-(IC3-DNC-Pad6)") (class "Default")
      (node (ref "IC3") (pin "6") (pinfunction "DNC_6") (pintype "power_in"))
    )
    (net (code "147") (name "unconnected-(IC3-DNC-Pad7)") (class "Default")
      (node (ref "IC3") (pin "7") (pinfunction "DNC_7") (pintype "power_in"))
    )
    (net (code "148") (name "unconnected-(IC3-DNC-Pad8)") (class "Default")
      (node (ref "IC3") (pin "8") (pinfunction "DNC_8") (pintype "power_in"))
    )
    (net (code "149") (name "unconnected-(IC3-Xout-Pad2)") (class "Default")
      (node (ref "IC3") (pin "2") (pinfunction "Xout_2") (pintype "power_in"))
    )
    (net (code "150") (name "unconnected-(IC4-GNDX-Pad35)") (class "Default")
      (node (ref "IC4") (pin "35") (pinfunction "GNDX_35") (pintype "power_in"))
    )
    (net (code "151") (name "unconnected-(IC4-OSC1-Pad41)") (class "Default")
      (node (ref "IC4") (pin "41") (pinfunction "OSC1_41") (pintype "input"))
    )
    (net (code "152") (name "unconnected-(IC4-PA3{slash}SSI0Fss-Pad20)") (class "Default")
      (node (ref "IC4") (pin "20") (pinfunction "PA3/SSI0Fss_20") (pintype "bidirectional"))
    )
    (net (code "153") (name "unconnected-(IC4-PA7-Pad24)") (class "Default")
      (node (ref "IC4") (pin "24") (pinfunction "PA7_24") (pintype "bidirectional"))
    )
    (net (code "154") (name "unconnected-(IC4-PB1{slash}USB0VBUS-Pad46)") (class "Default")
      (node (ref "IC4") (pin "46") (pinfunction "PB1/USB0VBUS_46") (pintype "bidirectional"))
    )
    (net (code "155") (name "unconnected-(IC4-PC7-Pad13)") (class "Default")
      (node (ref "IC4") (pin "13") (pinfunction "PC7_13") (pintype "bidirectional"))
    )
    (net (code "156") (name "unconnected-(IC4-PD1-Pad62)") (class "Default")
      (node (ref "IC4") (pin "62") (pinfunction "PD1_62") (pintype "bidirectional"))
    )
    (net (code "157") (name "unconnected-(IC4-PD3-Pad64)") (class "Default")
      (node (ref "IC4") (pin "64") (pinfunction "PD3_64") (pintype "bidirectional"))
    )
    (net (code "158") (name "unconnected-(IC4-PD7-Pad10)") (class "Default")
      (node (ref "IC4") (pin "10") (pinfunction "PD7_10") (pintype "bidirectional"))
    )
    (net (code "159") (name "unconnected-(IC4-PE1-Pad8)") (class "Default")
      (node (ref "IC4") (pin "8") (pinfunction "PE1_8") (pintype "bidirectional"))
    )
    (net (code "160") (name "unconnected-(IC4-PE3-Pad6)") (class "Default")
      (node (ref "IC4") (pin "6") (pinfunction "PE3_6") (pintype "bidirectional"))
    )
    (net (code "161") (name "unconnected-(IC4-PF4-Pad5)") (class "Default")
      (node (ref "IC4") (pin "5") (pinfunction "PF4_5") (pintype "bidirectional"))
    )
    (net (code "162") (name "unconnected-(IC4-XOSC0-Pad34)") (class "Default")
      (node (ref "IC4") (pin "34") (pinfunction "XOSC0_34") (pintype "input"))
    )
    (net (code "163") (name "unconnected-(IC4-XOSC1-Pad36)") (class "Default")
      (node (ref "IC4") (pin "36") (pinfunction "XOSC1_36") (pintype "input"))
    )
    (net (code "164") (name "unconnected-(IC4-~{HIB}-Pad33)") (class "Default")
      (node (ref "IC4") (pin "33") (pinfunction "~{HIB}_33") (pintype "bidirectional"))
    )
    (net (code "165") (name "unconnected-(IC4-~{WAKE}-Pad32)") (class "Default")
      (node (ref "IC4") (pin "32") (pinfunction "~{WAKE}_32") (pintype "bidirectional"))
    )
    (net (code "166") (name "unconnected-(IC5B-+Vs-Pad8)") (class "Default")
      (node (ref "IC5") (pin "8") (pinfunction "+Vs_8") (pintype "power_in"))
    )
    (net (code "167") (name "unconnected-(IC5B--Vs-Pad4)") (class "Default")
      (node (ref "IC5") (pin "4") (pinfunction "-Vs_4") (pintype "power_in"))
    )
    (net (code "168") (name "unconnected-(IC9-NC-Pad10)") (class "Default")
      (node (ref "IC9") (pin "10") (pinfunction "NC_10") (pintype "tri_state"))
    )
    (net (code "169") (name "unconnected-(IC9-NC-Pad11)") (class "Default")
      (node (ref "IC9") (pin "11") (pinfunction "NC_11") (pintype "tri_state"))
    )
    (net (code "170") (name "unconnected-(IC9-NC-Pad14)") (class "Default")
      (node (ref "IC9") (pin "14") (pinfunction "NC_14") (pintype "tri_state"))
    )
    (net (code "171") (name "unconnected-(IC12-NC-Pad1)") (class "Default")
      (node (ref "IC12") (pin "1") (pinfunction "NC_1") (pintype "passive"))
    )
    (net (code "172") (name "unconnected-(IC12-NC-Pad3)") (class "Default")
      (node (ref "IC12") (pin "3") (pinfunction "NC_3") (pintype "passive"))
    )
    (net (code "173") (name "unconnected-(IC12-NC-Pad7)") (class "Default")
      (node (ref "IC12") (pin "7") (pinfunction "NC_7") (pintype "passive"))
    )
    (net (code "174") (name "unconnected-(IC12-NC-Pad8)") (class "Default")
      (node (ref "IC12") (pin "8") (pinfunction "NC_8") (pintype "passive"))
    )
    (net (code "175") (name "unconnected-(IC13B-+Vs-Pad8)") (class "Default")
      (node (ref "IC13") (pin "8") (pinfunction "+Vs_8") (pintype "power_in"))
    )
    (net (code "176") (name "unconnected-(IC13B--Vs-Pad4)") (class "Default")
      (node (ref "IC13") (pin "4") (pinfunction "-Vs_4") (pintype "power_in"))
    )
    (net (code "177") (name "unconnected-(IC15-AGND-Pad10)") (class "Default")
      (node (ref "IC15") (pin "10") (pinfunction "AGND_10") (pintype "power_in"))
    )
    (net (code "178") (name "unconnected-(IC15-OTDR-Pad39)") (class "Default")
      (node (ref "IC15") (pin "39") (pinfunction "OTDR_39") (pintype "power_in"))
    )
    (net (code "179") (name "unconnected-(IC15-RSV3-Pad40)") (class "Default")
      (node (ref "IC15") (pin "40") (pinfunction "RSV3_40") (pintype "power_in"))
    )
    (net (code "180") (name "unconnected-(IC15-~{DOUT}-Pad43)") (class "Default")
      (node (ref "IC15") (pin "43") (pinfunction "~{DOUT}_43") (pintype "power_in"))
    )
    (net (code "181") (name "unconnected-(IC15-~{DRDY}-Pad45)") (class "Default")
      (node (ref "IC15") (pin "45") (pinfunction "~{DRDY}_45") (pintype "power_in"))
    )
    (net (code "182") (name "unconnected-(IC15-~{SCLK}-Pad41)") (class "Default")
      (node (ref "IC15") (pin "41") (pinfunction "~{SCLK}_41") (pintype "power_in"))
    )
    (net (code "183") (name "unconnected-(IC17-NC-Pad1)") (class "Default")
      (node (ref "IC17") (pin "1") (pinfunction "NC_1") (pintype "passive"))
    )
    (net (code "184") (name "unconnected-(IC17-NC-Pad3)") (class "Default")
      (node (ref "IC17") (pin "3") (pinfunction "NC_3") (pintype "passive"))
    )
    (net (code "185") (name "unconnected-(IC17-NC-Pad7)") (class "Default")
      (node (ref "IC17") (pin "7") (pinfunction "NC_7") (pintype "passive"))
    )
    (net (code "186") (name "unconnected-(IC17-NC-Pad8)") (class "Default")
      (node (ref "IC17") (pin "8") (pinfunction "NC_8") (pintype "passive"))
    )
    (net (code "187") (name "unconnected-(OSC1-NC{slash}TS-Pad8)") (class "Default")
      (node (ref "OSC1") (pin "8") (pinfunction "NC/TS_8") (pintype "passive"))
    )
  )
)
